# disciples_v1.net
KiCad netlist of a schematic drawn in EAGLE
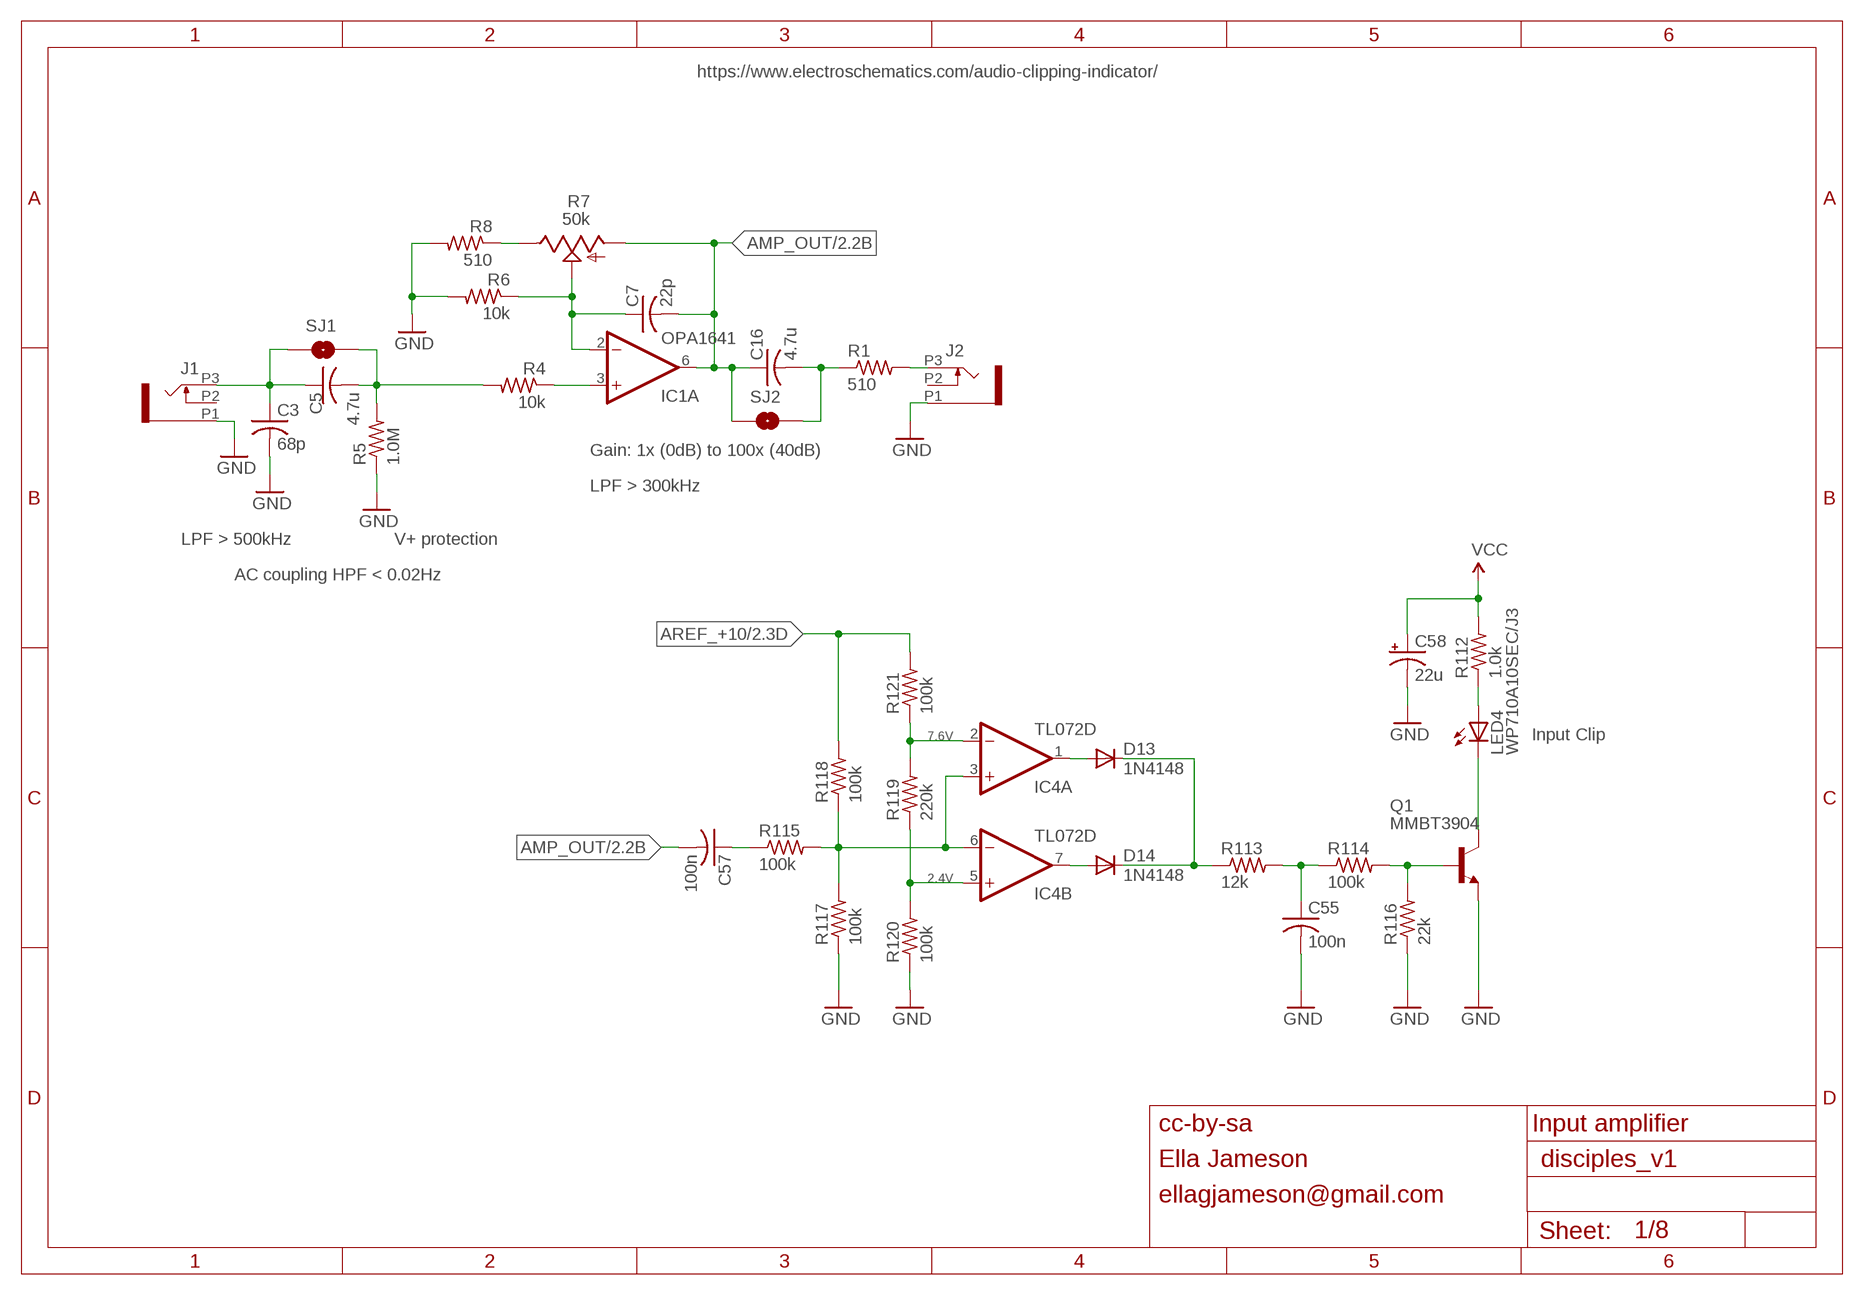
[diagram p0: schematic, sheet 1]
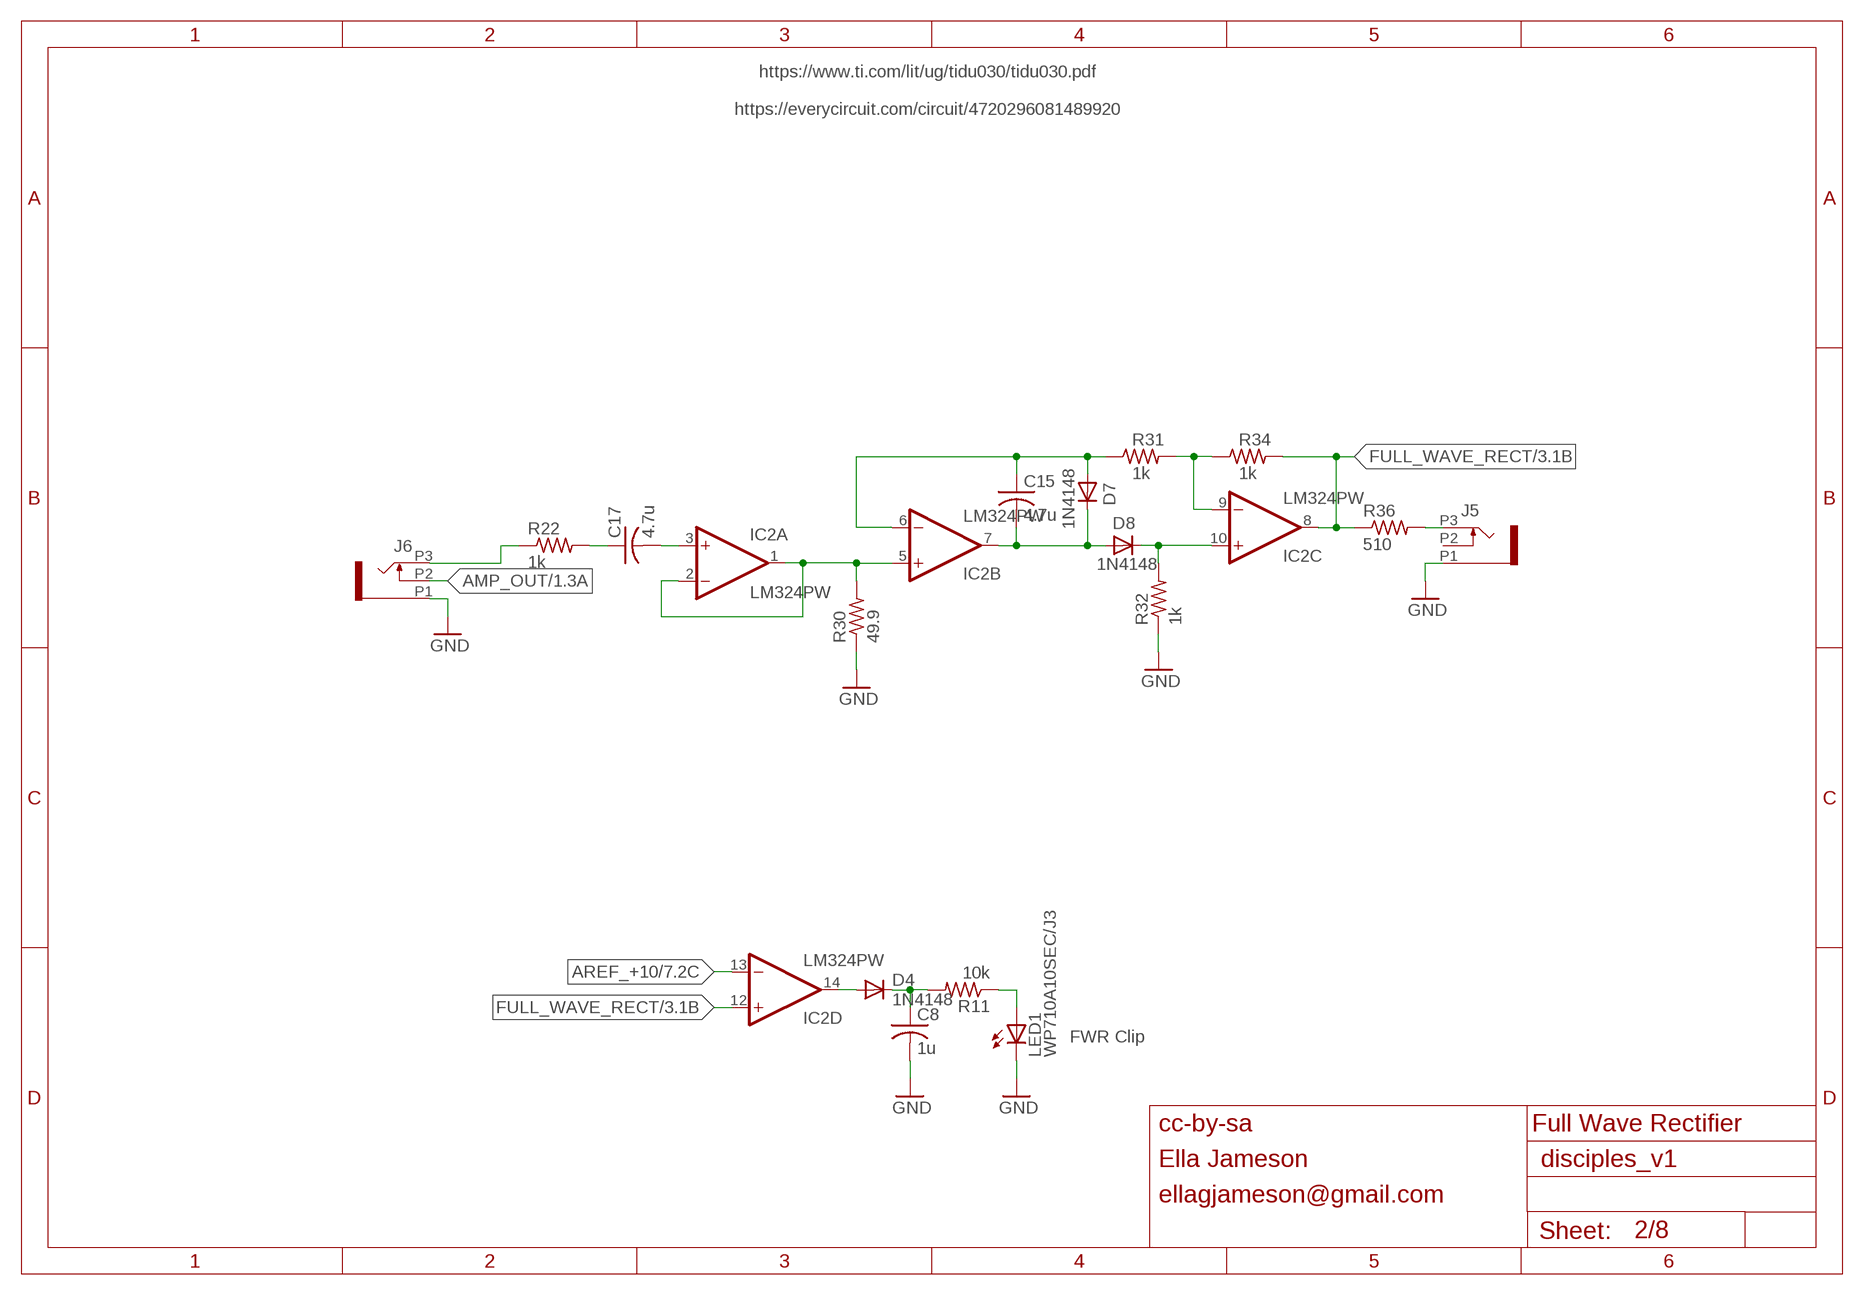
[diagram p1: schematic, sheet 2]
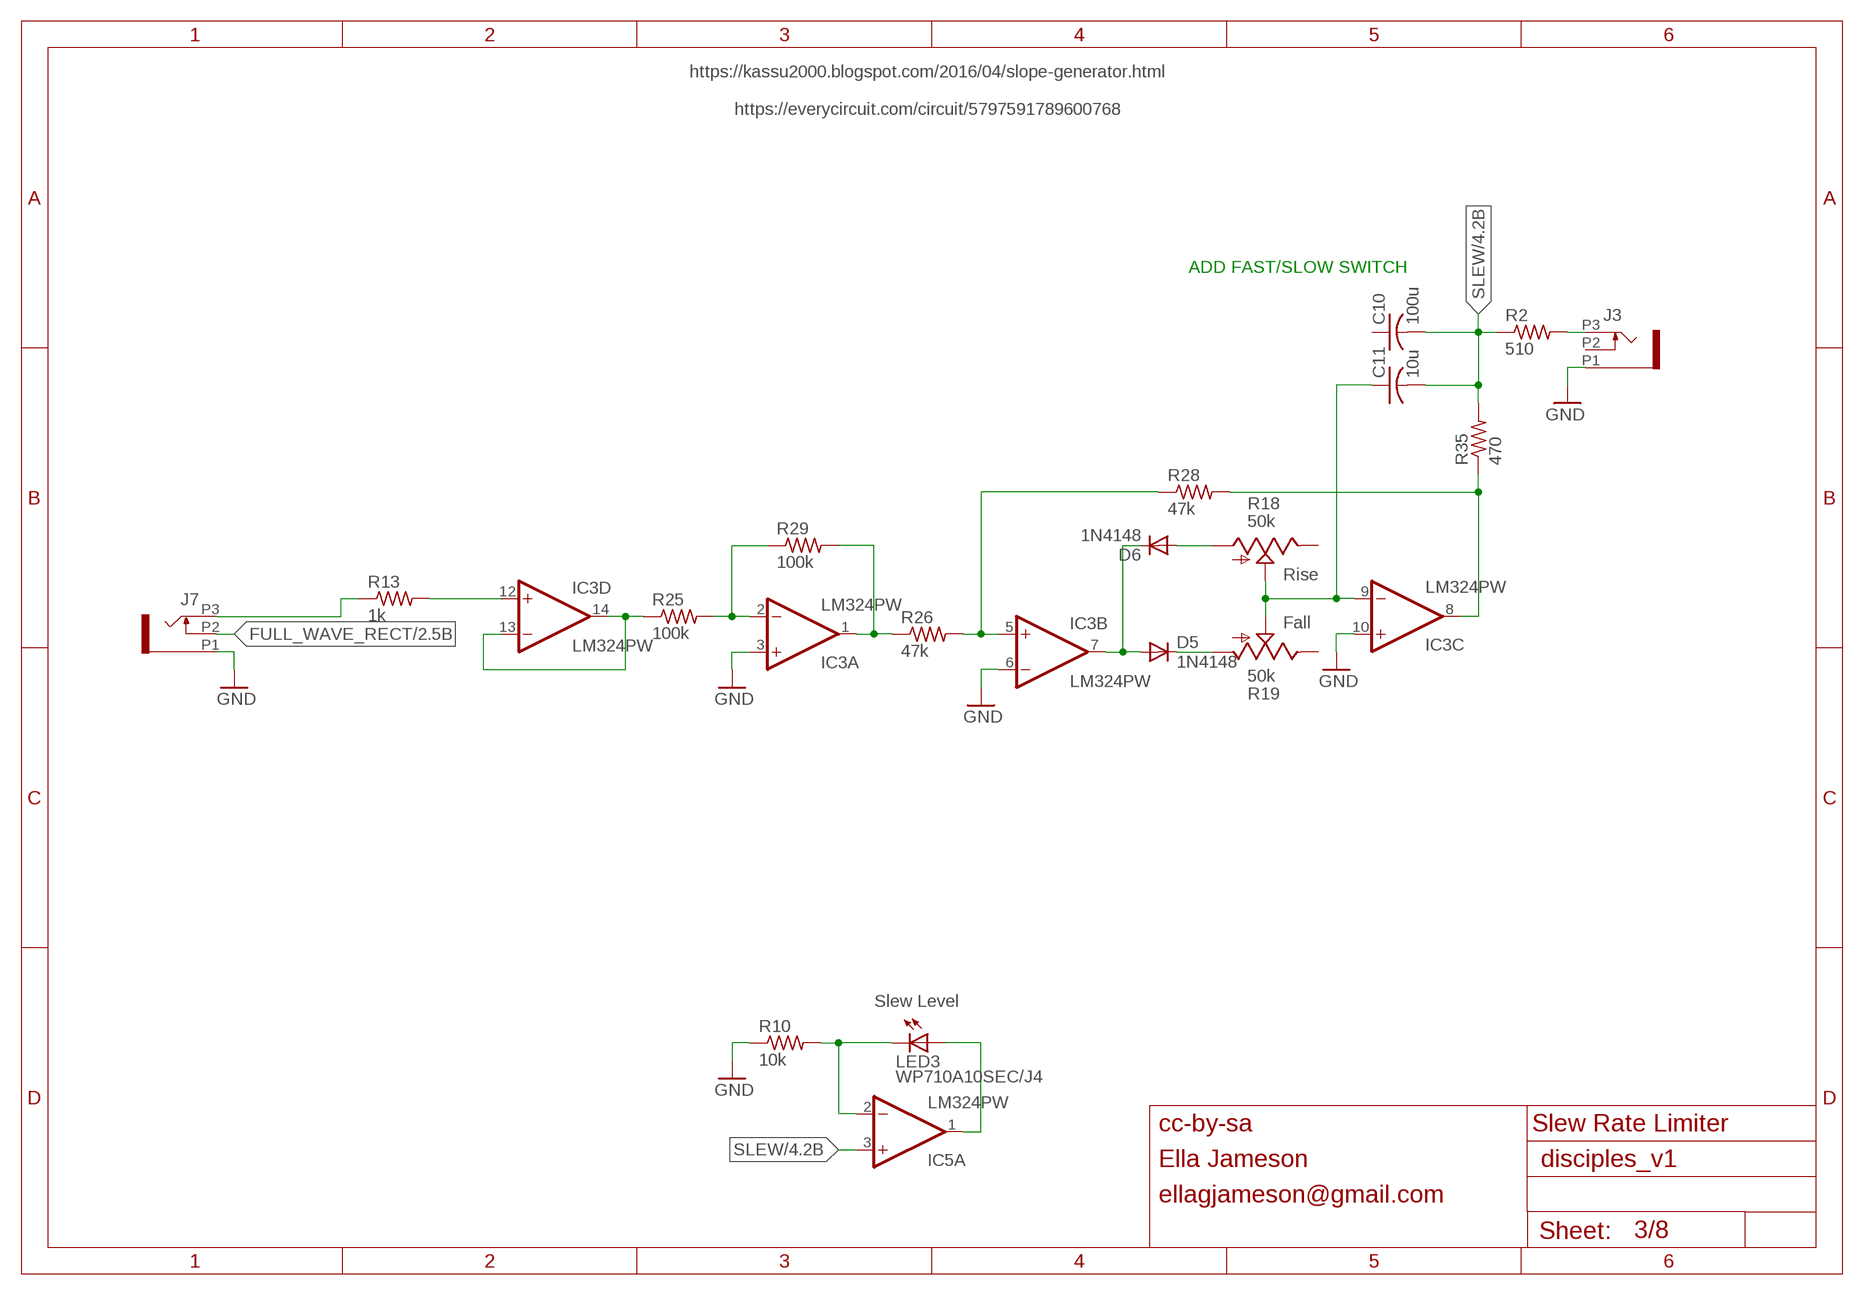
[diagram p2: schematic, sheet 3]
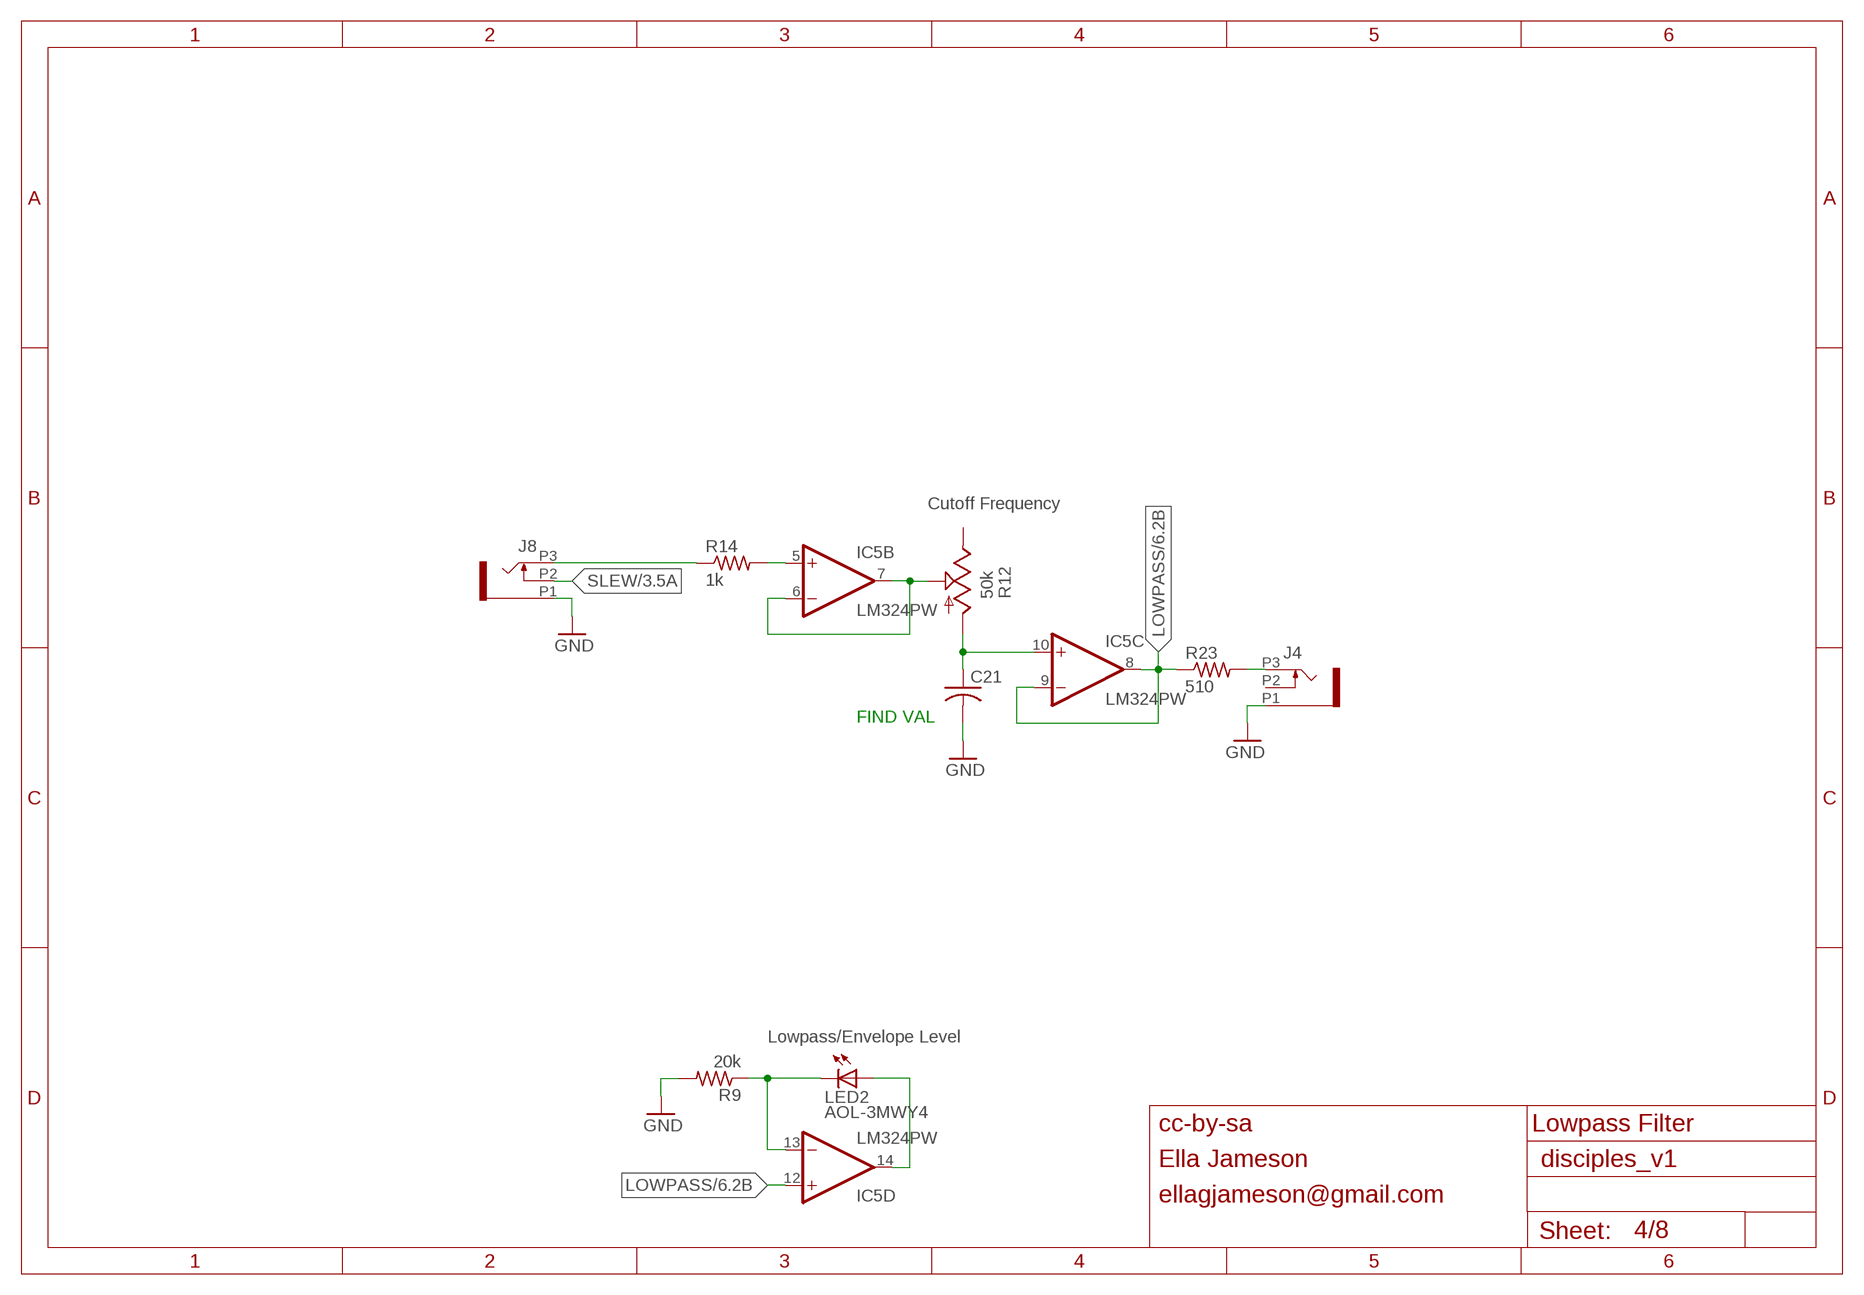
[diagram p3: schematic, sheet 4]
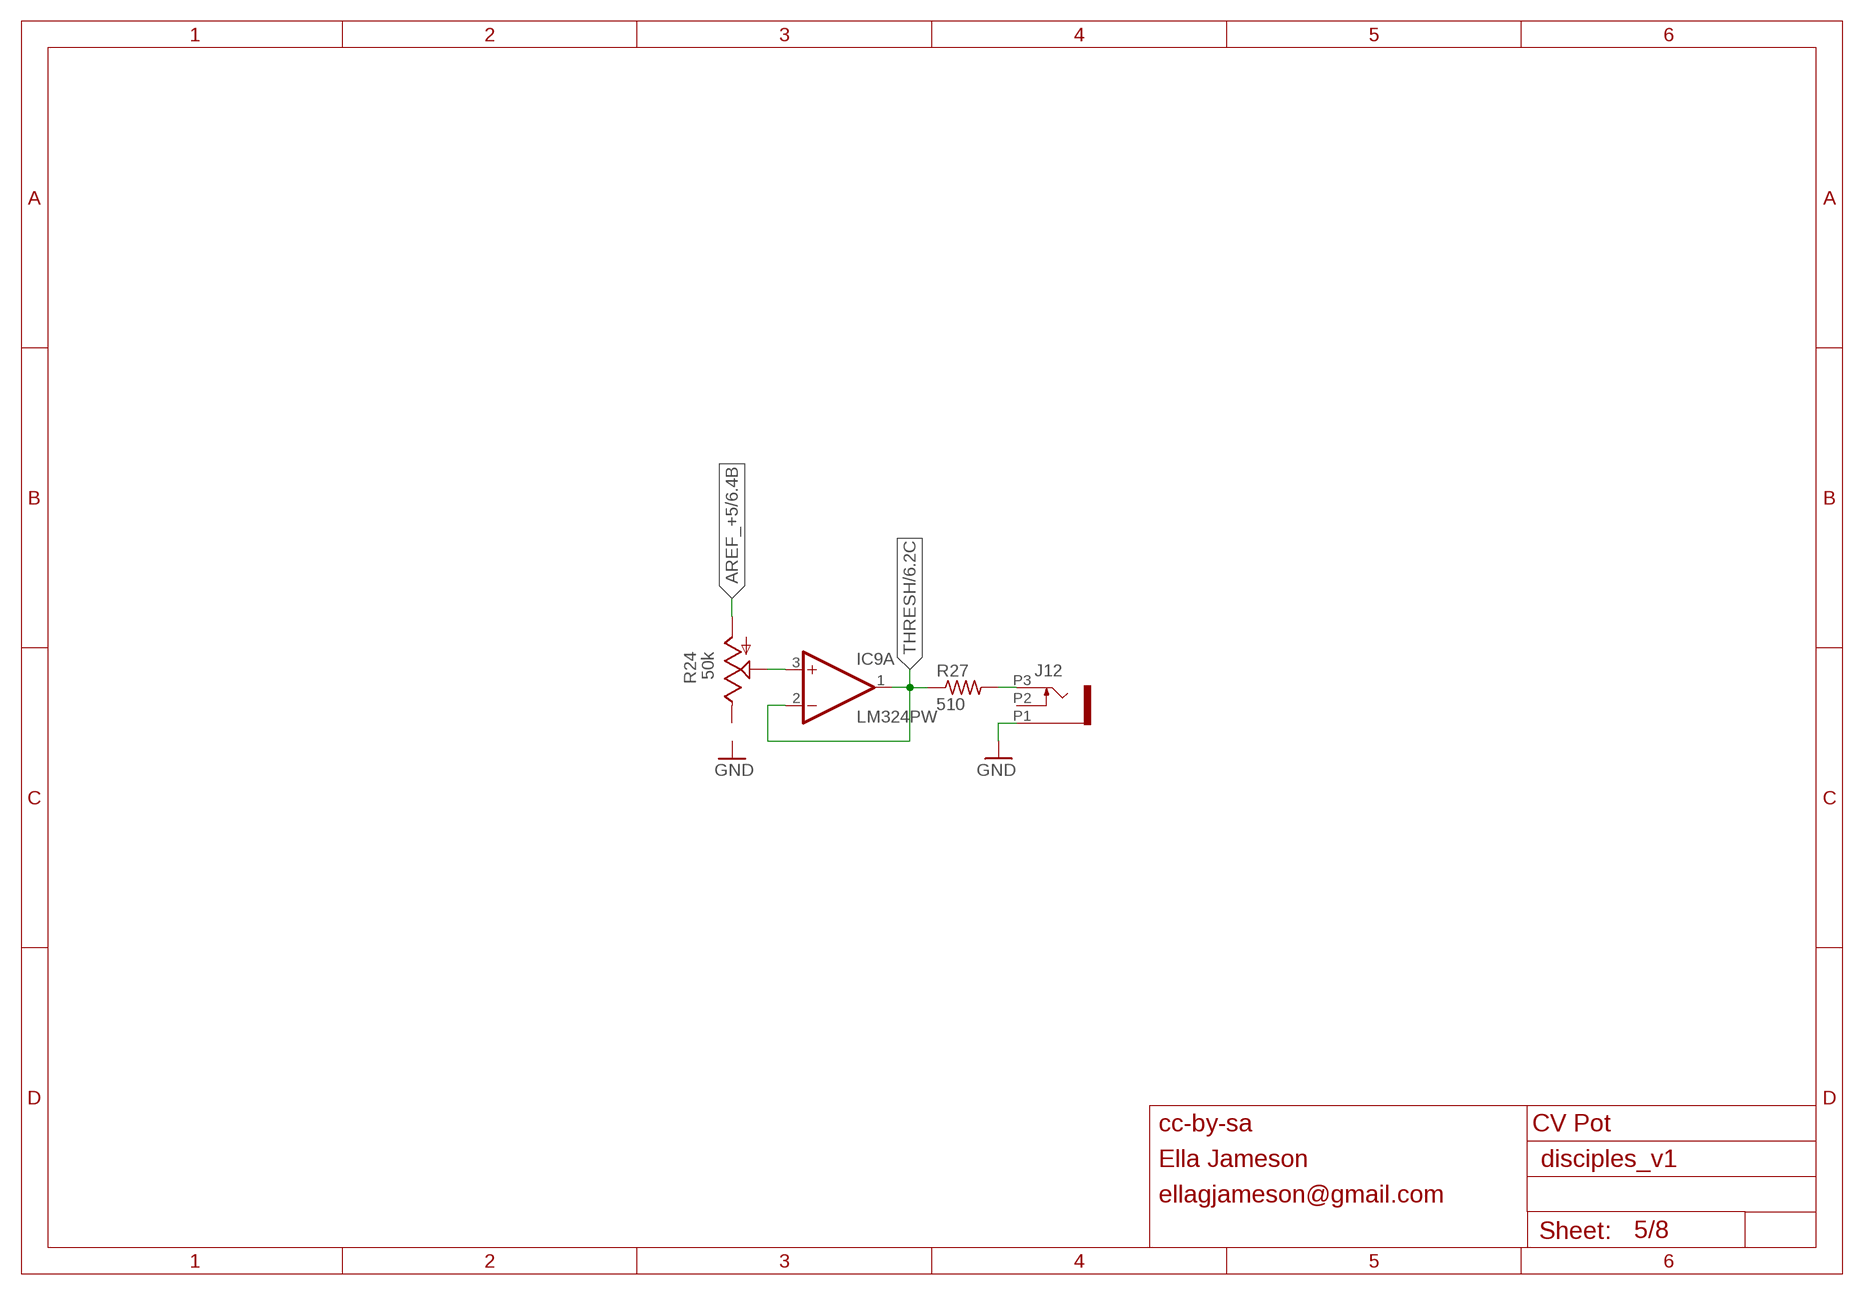
[diagram p4: schematic, sheet 5]
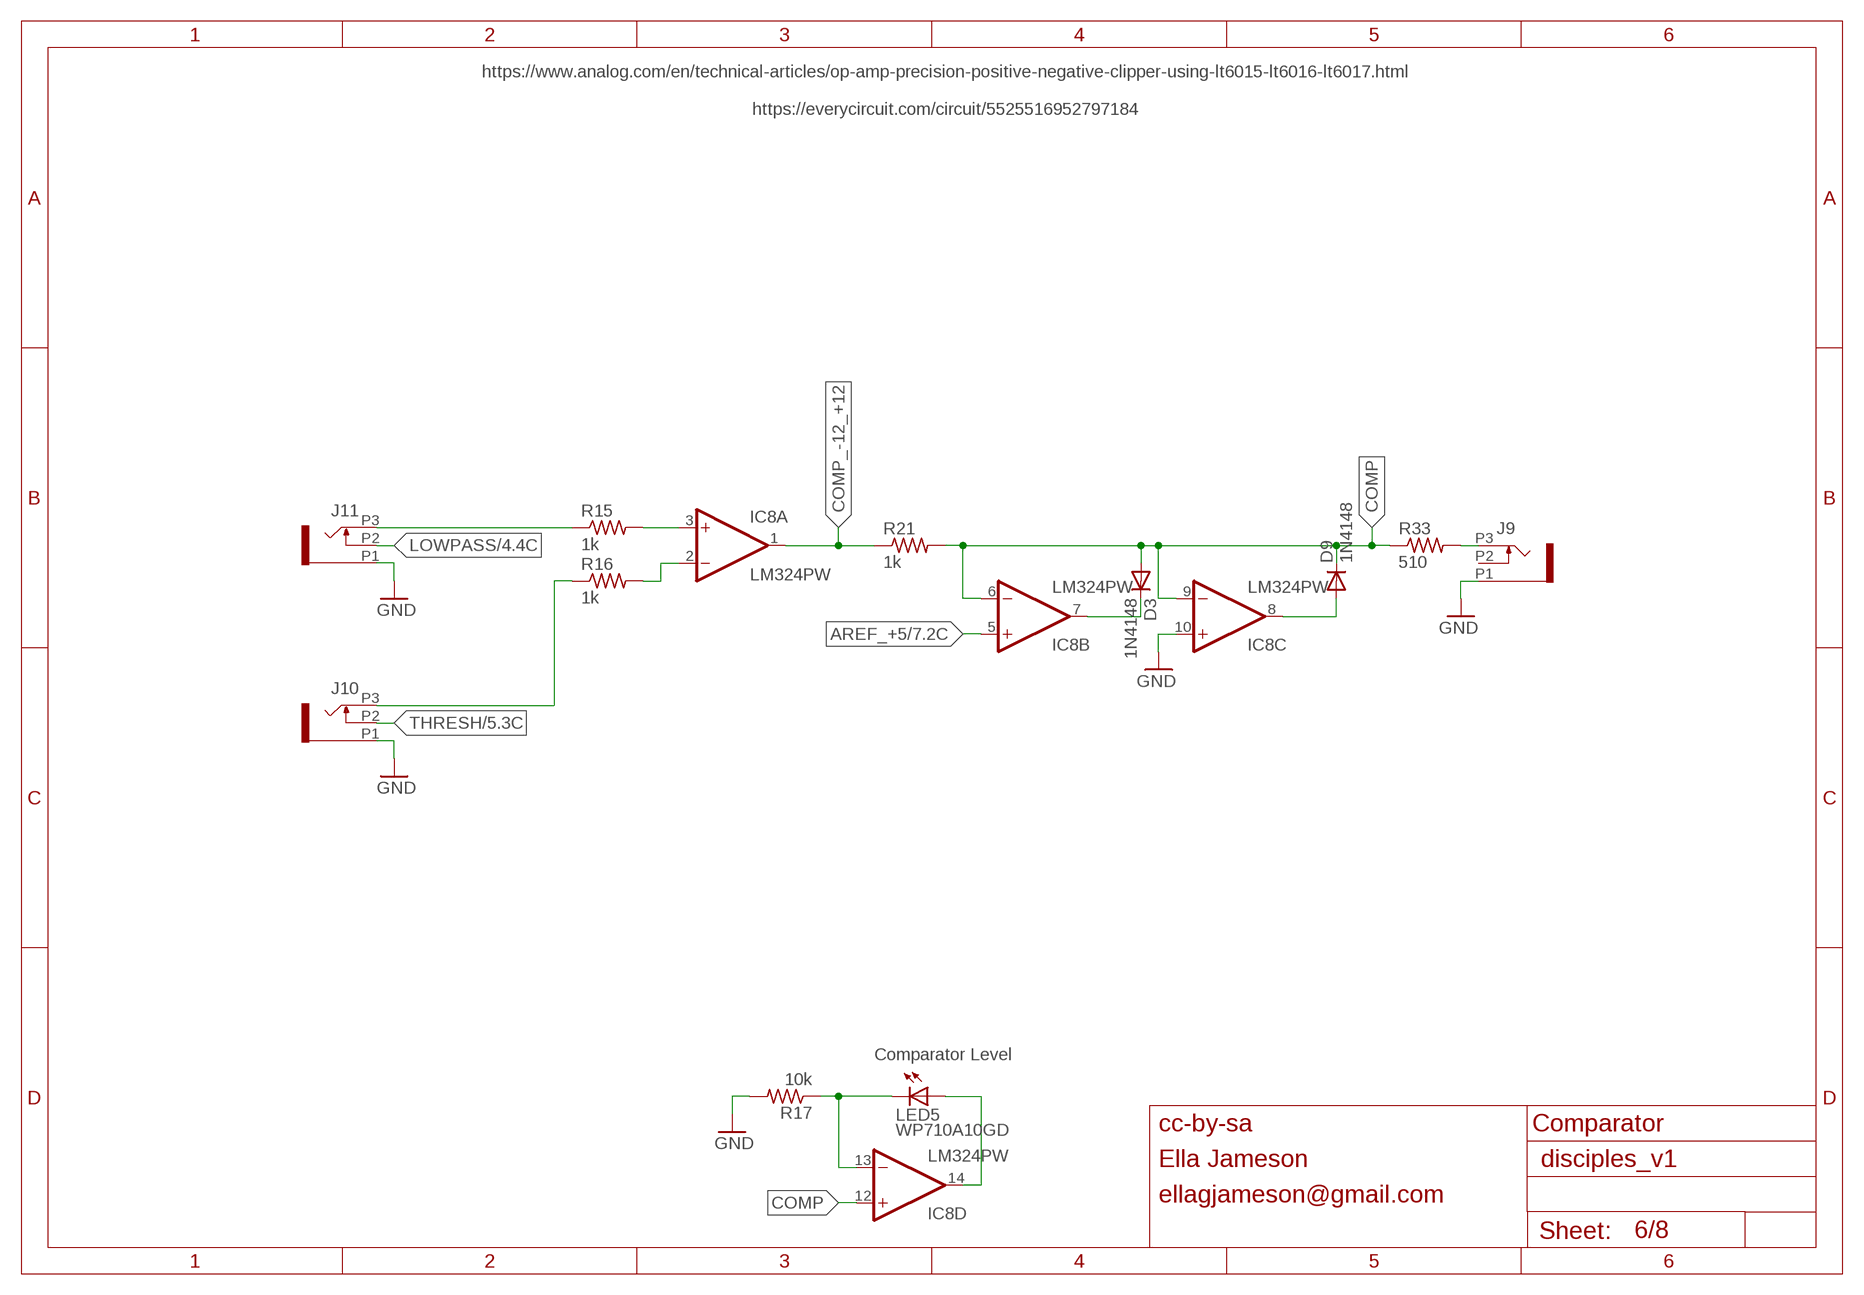
[diagram p5: schematic, sheet 6]
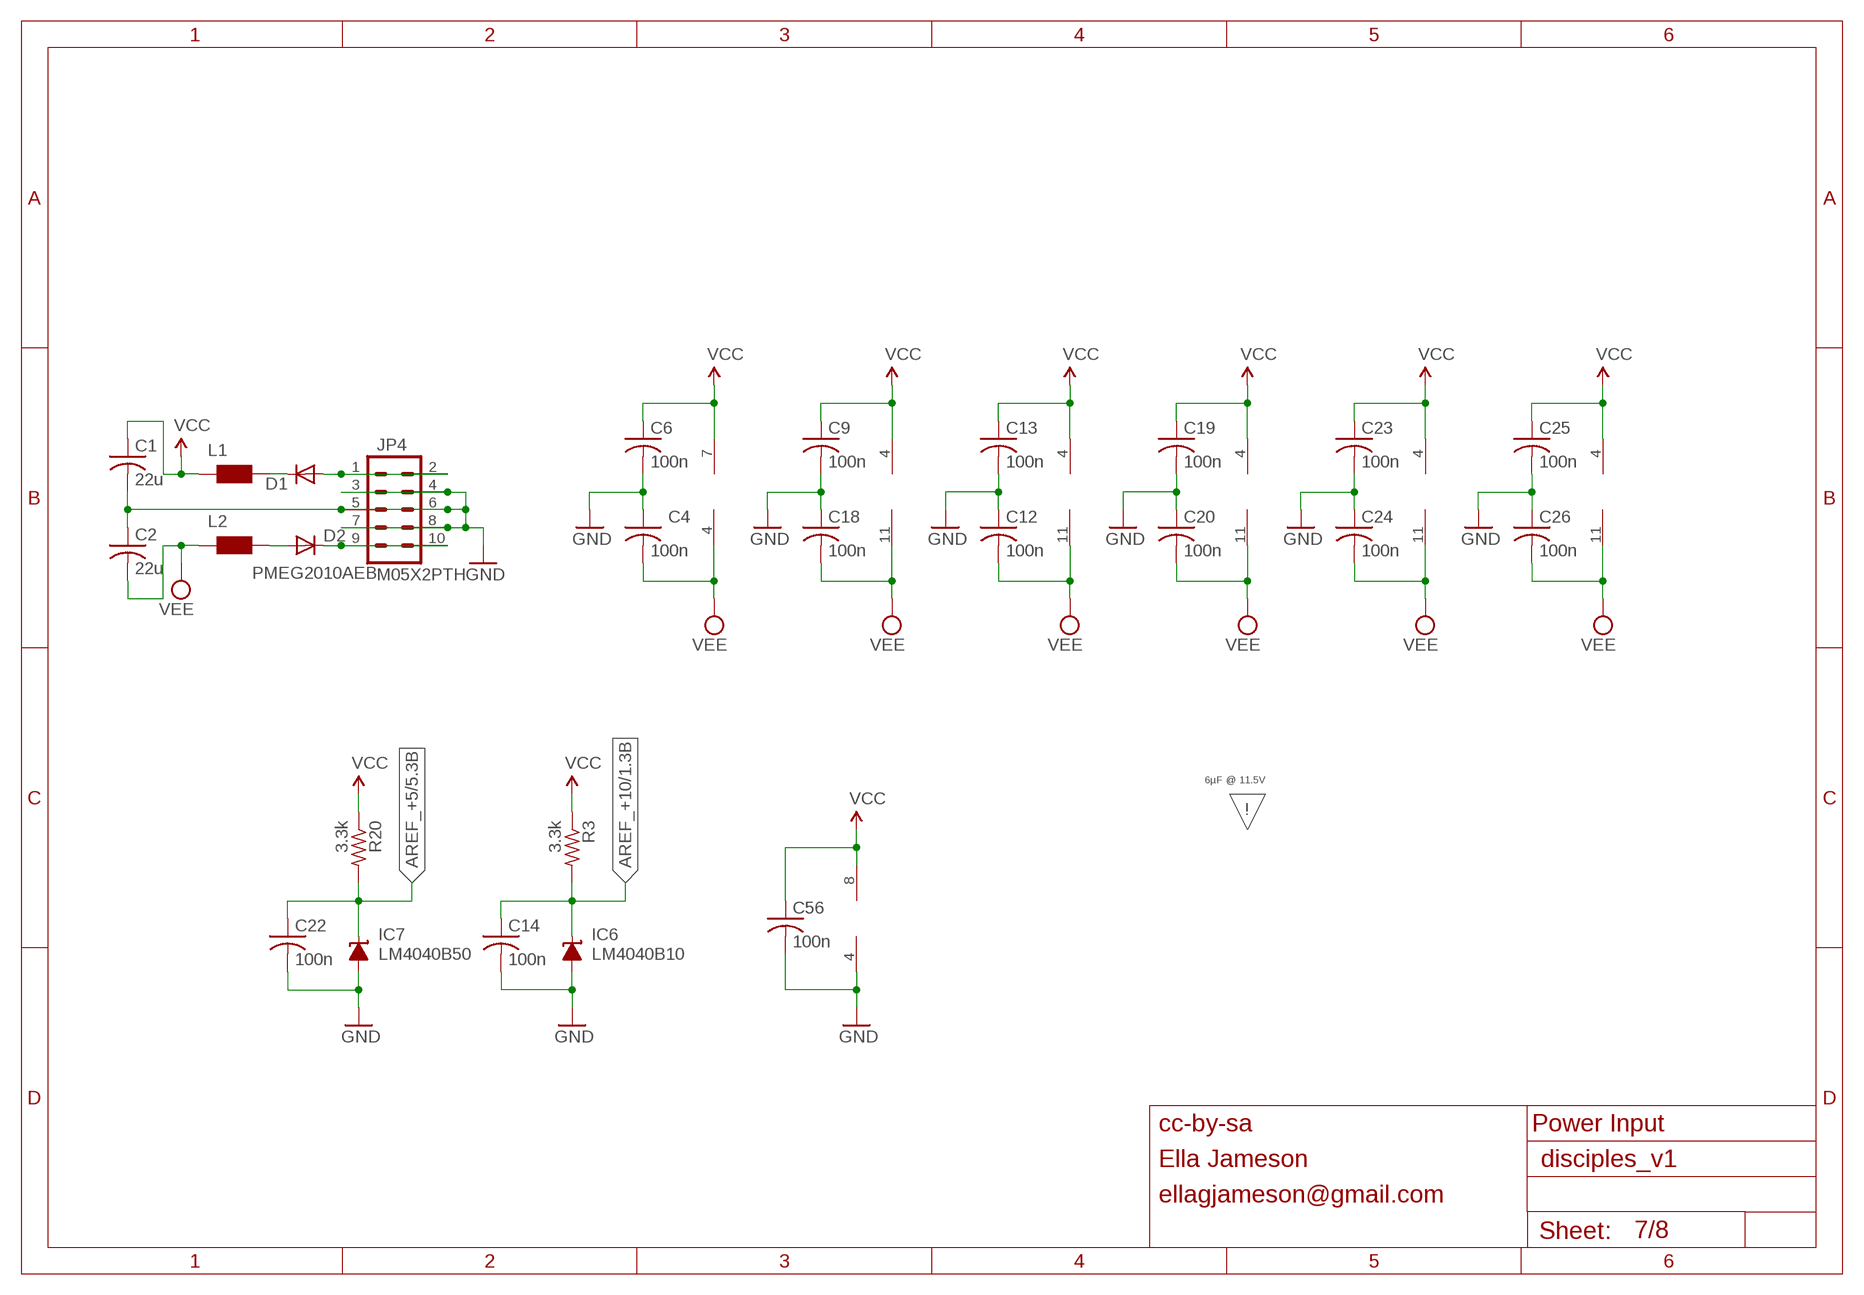
[diagram p6: schematic, sheet 7]
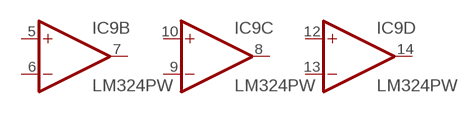
[diagram p7: schematic, sheet 8]

(export (version "E")
  (design (tool "Eeschema 10.0.6"))
  (components
    (comp (ref "D3")
      (value "1N4148")
      (footprint "eagle-import:SOD523")
      (libsource (lib "eagle-import") (part "DIODE-SOD523"))
    )
    (comp (ref "D9")
      (value "1N4148")
      (footprint "eagle-import:SOD523")
      (libsource (lib "eagle-import") (part "DIODE-SOD523"))
    )
    (comp (ref "IC8")
      (value "LM324PW")
      (footprint "eagle-import:TSSOP14")
      (libsource (lib "eagle-import") (part "LM324PW"))
    )
    (comp (ref "J9")
      (value "PJ301_THONKICONN6")
      (footprint "eagle-import:WQP_PJ_301M6")
      (libsource (lib "eagle-import") (part "PJ301_THONKICONN6"))
    )
    (comp (ref "J10")
      (value "PJ301_THONKICONN6")
      (footprint "eagle-import:WQP_PJ_301M6")
      (libsource (lib "eagle-import") (part "PJ301_THONKICONN6"))
    )
    (comp (ref "J11")
      (value "PJ301_THONKICONN6")
      (footprint "eagle-import:WQP_PJ_301M6")
      (libsource (lib "eagle-import") (part "PJ301_THONKICONN6"))
    )
    (comp (ref "LED5")
      (value "WP710A10GD")
      (footprint "eagle-import:LED3MM")
      (libsource (lib "eagle-import") (part "LED3MM"))
    )
    (comp (ref "R15")
      (value "1k")
      (footprint "eagle-import:R0402")
      (libsource (lib "eagle-import") (part "R-US_R0402"))
    )
    (comp (ref "R16")
      (value "1k")
      (footprint "eagle-import:R0402")
      (libsource (lib "eagle-import") (part "R-US_R0402"))
    )
    (comp (ref "R17")
      (value "10k")
      (footprint "eagle-import:R0402")
      (libsource (lib "eagle-import") (part "R-US_R0402"))
    )
    (comp (ref "R21")
      (value "1k")
      (footprint "eagle-import:R0402")
      (libsource (lib "eagle-import") (part "R-US_R0402"))
    )
    (comp (ref "R33")
      (value "510")
      (footprint "eagle-import:R0402")
      (libsource (lib "eagle-import") (part "R-US_R0402"))
    )
    (comp (ref "IC9")
      (value "LM324PW")
      (footprint "eagle-import:TSSOP14")
      (libsource (lib "eagle-import") (part "LM324PW"))
    )
    (comp (ref "J12")
      (value "PJ301_THONKICONN6")
      (footprint "eagle-import:WQP_PJ_301M6")
      (libsource (lib "eagle-import") (part "PJ301_THONKICONN6"))
    )
    (comp (ref "R24")
      (value "50k")
      (footprint "eagle-import:ALPS_POT_VERTICAL_PS")
      (libsource (lib "eagle-import") (part "POT_USVERTICAL_PS"))
    )
    (comp (ref "R27")
      (value "510")
      (footprint "eagle-import:R0402")
      (libsource (lib "eagle-import") (part "R-US_R0402"))
    )
    (comp (ref "C21")
      (value "C-USC0402")
      (footprint "eagle-import:C0402")
      (libsource (lib "eagle-import") (part "C-USC0402"))
    )
    (comp (ref "IC5")
      (value "LM324PW")
      (footprint "eagle-import:TSSOP14")
      (libsource (lib "eagle-import") (part "LM324PW"))
    )
    (comp (ref "J4")
      (value "PJ301_THONKICONN6")
      (footprint "eagle-import:WQP_PJ_301M6")
      (libsource (lib "eagle-import") (part "PJ301_THONKICONN6"))
    )
    (comp (ref "J8")
      (value "PJ301_THONKICONN6")
      (footprint "eagle-import:WQP_PJ_301M6")
      (libsource (lib "eagle-import") (part "PJ301_THONKICONN6"))
    )
    (comp (ref "LED2")
      (value "AOL-3MWY4")
      (footprint "eagle-import:LED3MM")
      (libsource (lib "eagle-import") (part "LED3MM"))
    )
    (comp (ref "R9")
      (value "20k")
      (footprint "eagle-import:R0402")
      (libsource (lib "eagle-import") (part "R-US_R0402"))
    )
    (comp (ref "R12")
      (value "50k")
      (footprint "eagle-import:ALPS_POT_VERTICAL_PS")
      (libsource (lib "eagle-import") (part "POT_USVERTICAL_PS"))
    )
    (comp (ref "R14")
      (value "1k")
      (footprint "eagle-import:R0402")
      (libsource (lib "eagle-import") (part "R-US_R0402"))
    )
    (comp (ref "R23")
      (value "510")
      (footprint "eagle-import:R0402")
      (libsource (lib "eagle-import") (part "R-US_R0402"))
    )
    (comp (ref "C8")
      (value "1u")
      (footprint "eagle-import:C0402")
      (libsource (lib "eagle-import") (part "C-USC0402"))
    )
    (comp (ref "C15")
      (value "4.7u")
      (footprint "eagle-import:C0603")
      (libsource (lib "eagle-import") (part "C-USC0603"))
    )
    (comp (ref "C17")
      (value "4.7u")
      (footprint "eagle-import:C0603")
      (libsource (lib "eagle-import") (part "C-USC0603"))
    )
    (comp (ref "D4")
      (value "1N4148")
      (footprint "eagle-import:SOD523")
      (libsource (lib "eagle-import") (part "DIODE-SOD523"))
    )
    (comp (ref "D7")
      (value "1N4148")
      (footprint "eagle-import:SOD523")
      (libsource (lib "eagle-import") (part "DIODE-SOD523"))
    )
    (comp (ref "D8")
      (value "1N4148")
      (footprint "eagle-import:SOD523")
      (libsource (lib "eagle-import") (part "DIODE-SOD523"))
    )
    (comp (ref "IC2")
      (value "LM324PW")
      (footprint "eagle-import:TSSOP14")
      (libsource (lib "eagle-import") (part "LM324PW"))
    )
    (comp (ref "J5")
      (value "PJ301_THONKICONN6")
      (footprint "eagle-import:WQP_PJ_301M6")
      (libsource (lib "eagle-import") (part "PJ301_THONKICONN6"))
    )
    (comp (ref "J6")
      (value "PJ301_THONKICONN6")
      (footprint "eagle-import:WQP_PJ_301M6")
      (libsource (lib "eagle-import") (part "PJ301_THONKICONN6"))
    )
    (comp (ref "LED1")
      (value "WP710A10SEC/J3")
      (footprint "eagle-import:LED3MM")
      (libsource (lib "eagle-import") (part "LED3MM"))
    )
    (comp (ref "R11")
      (value "10k")
      (footprint "eagle-import:R0402")
      (libsource (lib "eagle-import") (part "R-US_R0402"))
    )
    (comp (ref "R22")
      (value "1k")
      (footprint "eagle-import:R0402")
      (libsource (lib "eagle-import") (part "R-US_R0402"))
    )
    (comp (ref "R30")
      (value "49.9")
      (footprint "eagle-import:R0402")
      (libsource (lib "eagle-import") (part "R-US_R0402"))
    )
    (comp (ref "R31")
      (value "1k")
      (footprint "eagle-import:R0402")
      (libsource (lib "eagle-import") (part "R-US_R0402"))
    )
    (comp (ref "R32")
      (value "1k")
      (footprint "eagle-import:R0402")
      (libsource (lib "eagle-import") (part "R-US_R0402"))
    )
    (comp (ref "R34")
      (value "1k")
      (footprint "eagle-import:R0402")
      (libsource (lib "eagle-import") (part "R-US_R0402"))
    )
    (comp (ref "R36")
      (value "510")
      (footprint "eagle-import:R0402")
      (libsource (lib "eagle-import") (part "R-US_R0402"))
    )
    (comp (ref "C1")
      (value "22u")
      (footprint "eagle-import:C1206")
      (libsource (lib "eagle-import") (part "C-USC1206"))
    )
    (comp (ref "C2")
      (value "22u")
      (footprint "eagle-import:C1206")
      (libsource (lib "eagle-import") (part "C-USC1206"))
    )
    (comp (ref "C4")
      (value "100n")
      (footprint "eagle-import:C0402")
      (libsource (lib "eagle-import") (part "C-USC0402"))
    )
    (comp (ref "C6")
      (value "100n")
      (footprint "eagle-import:C0402")
      (libsource (lib "eagle-import") (part "C-USC0402"))
    )
    (comp (ref "C9")
      (value "100n")
      (footprint "eagle-import:C0402")
      (libsource (lib "eagle-import") (part "C-USC0402"))
    )
    (comp (ref "C12")
      (value "100n")
      (footprint "eagle-import:C0402")
      (libsource (lib "eagle-import") (part "C-USC0402"))
    )
    (comp (ref "C13")
      (value "100n")
      (footprint "eagle-import:C0402")
      (libsource (lib "eagle-import") (part "C-USC0402"))
    )
    (comp (ref "C14")
      (value "100n")
      (footprint "eagle-import:C0603")
      (libsource (lib "eagle-import") (part "C-USC0603"))
    )
    (comp (ref "C18")
      (value "100n")
      (footprint "eagle-import:C0402")
      (libsource (lib "eagle-import") (part "C-USC0402"))
    )
    (comp (ref "C19")
      (value "100n")
      (footprint "eagle-import:C0402")
      (libsource (lib "eagle-import") (part "C-USC0402"))
    )
    (comp (ref "C20")
      (value "100n")
      (footprint "eagle-import:C0402")
      (libsource (lib "eagle-import") (part "C-USC0402"))
    )
    (comp (ref "C22")
      (value "100n")
      (footprint "eagle-import:C0603")
      (libsource (lib "eagle-import") (part "C-USC0603"))
    )
    (comp (ref "C23")
      (value "100n")
      (footprint "eagle-import:C0402")
      (libsource (lib "eagle-import") (part "C-USC0402"))
    )
    (comp (ref "C24")
      (value "100n")
      (footprint "eagle-import:C0402")
      (libsource (lib "eagle-import") (part "C-USC0402"))
    )
    (comp (ref "C25")
      (value "100n")
      (footprint "eagle-import:C0402")
      (libsource (lib "eagle-import") (part "C-USC0402"))
    )
    (comp (ref "C26")
      (value "100n")
      (footprint "eagle-import:C0402")
      (libsource (lib "eagle-import") (part "C-USC0402"))
    )
    (comp (ref "C56")
      (value "100n")
      (footprint "eagle-import:C0603")
      (libsource (lib "eagle-import") (part "C-USC0603"))
    )
    (comp (ref "D1")
      (value "PMEG2010AEB")
      (footprint "eagle-import:SOD523")
      (libsource (lib "eagle-import") (part "DIODE-SOD523"))
    )
    (comp (ref "D2")
      (value "PMEG2010AEB")
      (footprint "eagle-import:SOD523")
      (libsource (lib "eagle-import") (part "DIODE-SOD523"))
    )
    (comp (ref "IC1")
      (value "OPA1641")
      (footprint "eagle-import:MSOP8")
      (libsource (lib "eagle-import") (part "OPA1641"))
    )
    (comp (ref "IC3")
      (value "LM324PW")
      (footprint "eagle-import:TSSOP14")
      (libsource (lib "eagle-import") (part "LM324PW"))
    )
    (comp (ref "IC4")
      (value "TL072D")
      (footprint "eagle-import:SO08")
      (libsource (lib "eagle-import") (part "TL072D"))
    )
    (comp (ref "IC6")
      (value "LM4040B10")
      (footprint "eagle-import:DBZ_R-PDSO-G3")
      (libsource (lib "eagle-import") (part "LM4041DBZB12"))
    )
    (comp (ref "IC7")
      (value "LM4040B50")
      (footprint "eagle-import:DBZ_R-PDSO-G3")
      (libsource (lib "eagle-import") (part "LM4041DBZB12"))
    )
    (comp (ref "JP4")
      (value "M05X2PTH")
      (footprint "eagle-import:AVR_ICSP")
      (libsource (lib "eagle-import") (part "M05X2PTH"))
    )
    (comp (ref "L1")
      (value "WE-CBF_0603")
      (footprint "eagle-import:0603")
      (libsource (lib "eagle-import") (part "WE-CBF_0603"))
    )
    (comp (ref "L2")
      (value "WE-CBF_0603")
      (footprint "eagle-import:0603")
      (libsource (lib "eagle-import") (part "WE-CBF_0603"))
    )
    (comp (ref "R3")
      (value "3.3k")
      (footprint "eagle-import:R0603")
      (libsource (lib "eagle-import") (part "R-US_R0603"))
    )
    (comp (ref "R20")
      (value "3.3k")
      (footprint "eagle-import:R0603")
      (libsource (lib "eagle-import") (part "R-US_R0603"))
    )
    (comp (ref "C10")
      (value "100u")
      (footprint "eagle-import:C0402")
      (libsource (lib "eagle-import") (part "C-USC0402"))
    )
    (comp (ref "C11")
      (value "10u")
      (footprint "eagle-import:C0402")
      (libsource (lib "eagle-import") (part "C-USC0402"))
    )
    (comp (ref "D5")
      (value "1N4148")
      (footprint "eagle-import:SOD523")
      (libsource (lib "eagle-import") (part "DIODE-SOD523"))
    )
    (comp (ref "D6")
      (value "1N4148")
      (footprint "eagle-import:SOD523")
      (libsource (lib "eagle-import") (part "DIODE-SOD523"))
    )
    (comp (ref "J3")
      (value "PJ301_THONKICONN6")
      (footprint "eagle-import:WQP_PJ_301M6")
      (libsource (lib "eagle-import") (part "PJ301_THONKICONN6"))
    )
    (comp (ref "J7")
      (value "PJ301_THONKICONN6")
      (footprint "eagle-import:WQP_PJ_301M6")
      (libsource (lib "eagle-import") (part "PJ301_THONKICONN6"))
    )
    (comp (ref "LED3")
      (value "WP710A10SEC/J4")
      (footprint "eagle-import:LED3MM")
      (libsource (lib "eagle-import") (part "LED3MM"))
    )
    (comp (ref "R2")
      (value "510")
      (footprint "eagle-import:R0402")
      (libsource (lib "eagle-import") (part "R-US_R0402"))
    )
    (comp (ref "R10")
      (value "10k")
      (footprint "eagle-import:R0402")
      (libsource (lib "eagle-import") (part "R-US_R0402"))
    )
    (comp (ref "R13")
      (value "1k")
      (footprint "eagle-import:R0402")
      (libsource (lib "eagle-import") (part "R-US_R0402"))
    )
    (comp (ref "R18")
      (value "50k")
      (footprint "eagle-import:ALPS_POT_VERTICAL_PS")
      (libsource (lib "eagle-import") (part "POT_USVERTICAL_PS"))
    )
    (comp (ref "R19")
      (value "50k")
      (footprint "eagle-import:ALPS_POT_VERTICAL_PS")
      (libsource (lib "eagle-import") (part "POT_USVERTICAL_PS"))
    )
    (comp (ref "R25")
      (value "100k")
      (footprint "eagle-import:R0402")
      (libsource (lib "eagle-import") (part "R-US_R0402"))
    )
    (comp (ref "R26")
      (value "47k")
      (footprint "eagle-import:R0402")
      (libsource (lib "eagle-import") (part "R-US_R0402"))
    )
    (comp (ref "R28")
      (value "47k")
      (footprint "eagle-import:R0402")
      (libsource (lib "eagle-import") (part "R-US_R0402"))
    )
    (comp (ref "R29")
      (value "100k")
      (footprint "eagle-import:R0402")
      (libsource (lib "eagle-import") (part "R-US_R0402"))
    )
    (comp (ref "R35")
      (value "470")
      (footprint "eagle-import:R0402")
      (libsource (lib "eagle-import") (part "R-US_R0402"))
    )
    (comp (ref "C3")
      (value "68p")
      (footprint "eagle-import:C0402")
      (libsource (lib "eagle-import") (part "C-USC0402"))
    )
    (comp (ref "C5")
      (value "4.7u")
      (footprint "eagle-import:C0603")
      (libsource (lib "eagle-import") (part "C-USC0603"))
    )
    (comp (ref "C7")
      (value "22p")
      (footprint "eagle-import:C0402")
      (libsource (lib "eagle-import") (part "C-USC0402"))
    )
    (comp (ref "C16")
      (value "4.7u")
      (footprint "eagle-import:C0603")
      (libsource (lib "eagle-import") (part "C-USC0603"))
    )
    (comp (ref "C55")
      (value "100n")
      (footprint "eagle-import:C0603")
      (libsource (lib "eagle-import") (part "C-USC0603"))
    )
    (comp (ref "C57")
      (value "100n")
      (footprint "eagle-import:C0603")
      (libsource (lib "eagle-import") (part "C-USC0603"))
    )
    (comp (ref "C58")
      (value "22u")
      (footprint "eagle-import:PANASONIC_C")
      (libsource (lib "eagle-import") (part "CPOL-USC"))
    )
    (comp (ref "D13")
      (value "1N4148")
      (footprint "eagle-import:SOD323-W")
      (libsource (lib "eagle-import") (part "DIODE-SOD323-W"))
    )
    (comp (ref "D14")
      (value "1N4148")
      (footprint "eagle-import:SOD323-W")
      (libsource (lib "eagle-import") (part "DIODE-SOD323-W"))
    )
    (comp (ref "J1")
      (value "PJ301_THONKICONN6")
      (footprint "eagle-import:WQP_PJ_301M6")
      (libsource (lib "eagle-import") (part "PJ301_THONKICONN6"))
    )
    (comp (ref "J2")
      (value "PJ301_THONKICONN6")
      (footprint "eagle-import:WQP_PJ_301M6")
      (libsource (lib "eagle-import") (part "PJ301_THONKICONN6"))
    )
    (comp (ref "LED4")
      (value "WP710A10SEC/J3")
      (footprint "eagle-import:LED3MM")
      (libsource (lib "eagle-import") (part "LED3MM"))
    )
    (comp (ref "Q1")
      (value "MMBT3904")
      (footprint "eagle-import:SOT23-BEC")
      (libsource (lib "eagle-import") (part "-NPN-SOT23-BECMMBT3904LT1"))
    )
    (comp (ref "R1")
      (value "510")
      (footprint "eagle-import:R0402")
      (libsource (lib "eagle-import") (part "R-US_R0402"))
    )
    (comp (ref "R4")
      (value "10k")
      (footprint "eagle-import:R0402")
      (libsource (lib "eagle-import") (part "R-US_R0402"))
    )
    (comp (ref "R5")
      (value "1.0M")
      (footprint "eagle-import:R0402")
      (libsource (lib "eagle-import") (part "R-US_R0402"))
    )
    (comp (ref "R6")
      (value "10k")
      (footprint "eagle-import:R0402")
      (libsource (lib "eagle-import") (part "R-US_R0402"))
    )
    (comp (ref "R7")
      (value "50k")
      (footprint "eagle-import:ALPS_POT_VERTICAL_PS")
      (libsource (lib "eagle-import") (part "POT_USVERTICAL_PS"))
    )
    (comp (ref "R8")
      (value "510")
      (footprint "eagle-import:R0402")
      (libsource (lib "eagle-import") (part "R-US_R0402"))
    )
    (comp (ref "R112")
      (value "1.0k")
      (footprint "eagle-import:R0603")
      (libsource (lib "eagle-import") (part "R-US_R0603"))
    )
    (comp (ref "R113")
      (value "12k")
      (footprint "eagle-import:R0603")
      (libsource (lib "eagle-import") (part "R-US_R0603"))
    )
    (comp (ref "R114")
      (value "100k")
      (footprint "eagle-import:R0603")
      (libsource (lib "eagle-import") (part "R-US_R0603"))
    )
    (comp (ref "R115")
      (value "100k")
      (footprint "eagle-import:R0603")
      (libsource (lib "eagle-import") (part "R-US_R0603"))
    )
    (comp (ref "R116")
      (value "22k")
      (footprint "eagle-import:R0603")
      (libsource (lib "eagle-import") (part "R-US_R0603"))
    )
    (comp (ref "R117")
      (value "100k")
      (footprint "eagle-import:R0603")
      (libsource (lib "eagle-import") (part "R-US_R0603"))
    )
    (comp (ref "R118")
      (value "100k")
      (footprint "eagle-import:R0603")
      (libsource (lib "eagle-import") (part "R-US_R0603"))
    )
    (comp (ref "R119")
      (value "220k")
      (footprint "eagle-import:R0603")
      (libsource (lib "eagle-import") (part "R-US_R0603"))
    )
    (comp (ref "R120")
      (value "100k")
      (footprint "eagle-import:R0603")
      (libsource (lib "eagle-import") (part "R-US_R0603"))
    )
    (comp (ref "R121")
      (value "100k")
      (footprint "eagle-import:R0603")
      (libsource (lib "eagle-import") (part "R-US_R0603"))
    )
    (comp (ref "SJ1")
      (value "SOLDERJUMPERNC")
      (footprint "eagle-import:SJ_2S")
      (libsource (lib "eagle-import") (part "SOLDERJUMPERNC"))
    )
    (comp (ref "SJ2")
      (value "SOLDERJUMPERNC")
      (footprint "eagle-import:SJ_2S")
      (libsource (lib "eagle-import") (part "SOLDERJUMPERNC"))
    )
  )
  (nets
    (net (code "1") (name "AMP_OUT") (class "Default")
      (node (ref "C16") (pin "1") (pinfunction "1_1") (pintype "passive"))
      (node (ref "C57") (pin "2") (pinfunction "2_2") (pintype "passive"))
      (node (ref "C7") (pin "2") (pinfunction "2_2") (pintype "passive"))
      (node (ref "IC1") (pin "6") (pinfunction "OUT_6") (pintype "output"))
      (node (ref "J6") (pin "P2") (pinfunction "2_P2") (pintype "passive"))
      (node (ref "R7") (pin "P$3") (pinfunction "A_P$3") (pintype "passive"))
      (node (ref "SJ2") (pin "1") (pinfunction "1_1") (pintype "passive"))
    )
    (net (code "2") (name "AREF_+5") (class "Default")
      (node (ref "C22") (pin "1") (pinfunction "1_1") (pintype "passive"))
      (node (ref "IC7") (pin "1") (pinfunction "C_1") (pintype "passive"))
      (node (ref "IC8") (pin "5") (pinfunction "+IN_5") (pintype "input"))
      (node (ref "R20") (pin "2") (pinfunction "2_2") (pintype "passive"))
      (node (ref "R24") (pin "P$3") (pinfunction "A_P$3") (pintype "passive"))
    )
    (net (code "3") (name "AREF_+10") (class "Default")
      (node (ref "C14") (pin "1") (pinfunction "1_1") (pintype "passive"))
      (node (ref "IC2") (pin "13") (pinfunction "-IN_13") (pintype "input"))
      (node (ref "IC6") (pin "1") (pinfunction "C_1") (pintype "passive"))
      (node (ref "R118") (pin "2") (pinfunction "2_2") (pintype "passive"))
      (node (ref "R121") (pin "2") (pinfunction "2_2") (pintype "passive"))
      (node (ref "R3") (pin "2") (pinfunction "2_2") (pintype "passive"))
    )
    (net (code "4") (name "COMP") (class "Default")
      (node (ref "D3") (pin "A") (pinfunction "A_A") (pintype "passive"))
      (node (ref "D9") (pin "C") (pinfunction "C_C") (pintype "passive"))
      (node (ref "IC8") (pin "12") (pinfunction "+IN_12") (pintype "input"))
      (node (ref "IC8") (pin "6") (pinfunction "-IN_6") (pintype "input"))
      (node (ref "IC8") (pin "9") (pinfunction "-IN_9") (pintype "input"))
      (node (ref "R21") (pin "2") (pinfunction "2_2") (pintype "passive"))
      (node (ref "R33") (pin "1") (pinfunction "1_1") (pintype "passive"))
    )
    (net (code "5") (name "COMP_-12_+12") (class "Default")
      (node (ref "IC8") (pin "1") (pinfunction "OUT_1") (pintype "output"))
      (node (ref "R21") (pin "1") (pinfunction "1_1") (pintype "passive"))
    )
    (net (code "6") (name "FULL_WAVE_RECT") (class "Default")
      (node (ref "IC2") (pin "12") (pinfunction "+IN_12") (pintype "input"))
      (node (ref "IC2") (pin "8") (pinfunction "OUT_8") (pintype "output"))
      (node (ref "J7") (pin "P2") (pinfunction "2_P2") (pintype "passive"))
      (node (ref "R34") (pin "2") (pinfunction "2_2") (pintype "passive"))
      (node (ref "R36") (pin "1") (pinfunction "1_1") (pintype "passive"))
    )
    (net (code "7") (name "GND") (class "Default")
      (node (ref "C1") (pin "2") (pinfunction "2_2") (pintype "passive"))
      (node (ref "C12") (pin "1") (pinfunction "1_1") (pintype "passive"))
      (node (ref "C13") (pin "2") (pinfunction "2_2") (pintype "passive"))
      (node (ref "C14") (pin "2") (pinfunction "2_2") (pintype "passive"))
      (node (ref "C18") (pin "1") (pinfunction "1_1") (pintype "passive"))
      (node (ref "C19") (pin "2") (pinfunction "2_2") (pintype "passive"))
      (node (ref "C2") (pin "1") (pinfunction "1_1") (pintype "passive"))
      (node (ref "C20") (pin "1") (pinfunction "1_1") (pintype "passive"))
      (node (ref "C21") (pin "2") (pinfunction "2_2") (pintype "passive"))
      (node (ref "C22") (pin "2") (pinfunction "2_2") (pintype "passive"))
      (node (ref "C23") (pin "2") (pinfunction "2_2") (pintype "passive"))
      (node (ref "C24") (pin "1") (pinfunction "1_1") (pintype "passive"))
      (node (ref "C25") (pin "2") (pinfunction "2_2") (pintype "passive"))
      (node (ref "C26") (pin "1") (pinfunction "1_1") (pintype "passive"))
      (node (ref "C3") (pin "2") (pinfunction "2_2") (pintype "passive"))
      (node (ref "C4") (pin "1") (pinfunction "1_1") (pintype "passive"))
      (node (ref "C55") (pin "2") (pinfunction "2_2") (pintype "passive"))
      (node (ref "C56") (pin "2") (pinfunction "2_2") (pintype "passive"))
      (node (ref "C58") (pin "-") (pinfunction "-_-") (pintype "passive"))
      (node (ref "C6") (pin "2") (pinfunction "2_2") (pintype "passive"))
      (node (ref "C8") (pin "2") (pinfunction "2_2") (pintype "passive"))
      (node (ref "C9") (pin "2") (pinfunction "2_2") (pintype "passive"))
      (node (ref "IC3") (pin "10") (pinfunction "+IN_10") (pintype "input"))
      (node (ref "IC3") (pin "3") (pinfunction "+IN_3") (pintype "input"))
      (node (ref "IC3") (pin "6") (pinfunction "-IN_6") (pintype "input"))
      (node (ref "IC4") (pin "4") (pinfunction "V-_4") (pintype "power_in"))
      (node (ref "IC6") (pin "2") (pinfunction "A_2") (pintype "passive"))
      (node (ref "IC7") (pin "2") (pinfunction "A_2") (pintype "passive"))
      (node (ref "IC8") (pin "10") (pinfunction "+IN_10") (pintype "input"))
      (node (ref "J1") (pin "P1") (pinfunction "1_P1") (pintype "passive"))
      (node (ref "J10") (pin "P1") (pinfunction "1_P1") (pintype "passive"))
      (node (ref "J11") (pin "P1") (pinfunction "1_P1") (pintype "passive"))
      (node (ref "J12") (pin "P1") (pinfunction "1_P1") (pintype "passive"))
      (node (ref "J2") (pin "P1") (pinfunction "1_P1") (pintype "passive"))
      (node (ref "J3") (pin "P1") (pinfunction "1_P1") (pintype "passive"))
      (node (ref "J4") (pin "P1") (pinfunction "1_P1") (pintype "passive"))
      (node (ref "J5") (pin "P1") (pinfunction "1_P1") (pintype "passive"))
      (node (ref "J6") (pin "P1") (pinfunction "1_P1") (pintype "passive"))
      (node (ref "J7") (pin "P1") (pinfunction "1_P1") (pintype "passive"))
      (node (ref "J8") (pin "P1") (pinfunction "1_P1") (pintype "passive"))
      (node (ref "J9") (pin "P1") (pinfunction "1_P1") (pintype "passive"))
      (node (ref "JP4") (pin "3") (pinfunction "3_3") (pintype "passive"))
      (node (ref "JP4") (pin "4") (pinfunction "4_4") (pintype "passive"))
      (node (ref "JP4") (pin "5") (pinfunction "5_5") (pintype "passive"))
      (node (ref "JP4") (pin "6") (pinfunction "6_6") (pintype "passive"))
      (node (ref "JP4") (pin "7") (pinfunction "7_7") (pintype "passive"))
      (node (ref "JP4") (pin "8") (pinfunction "8_8") (pintype "passive"))
      (node (ref "LED1") (pin "K") (pinfunction "C_K") (pintype "passive"))
      (node (ref "Q1") (pin "E") (pinfunction "E_E") (pintype "passive"))
      (node (ref "R10") (pin "1") (pinfunction "1_1") (pintype "passive"))
      (node (ref "R116") (pin "1") (pinfunction "1_1") (pintype "passive"))
      (node (ref "R117") (pin "1") (pinfunction "1_1") (pintype "passive"))
      (node (ref "R120") (pin "1") (pinfunction "1_1") (pintype "passive"))
      (node (ref "R17") (pin "2") (pinfunction "2_2") (pintype "passive"))
      (node (ref "R30") (pin "1") (pinfunction "1_1") (pintype "passive"))
      (node (ref "R32") (pin "1") (pinfunction "1_1") (pintype "passive"))
      (node (ref "R5") (pin "1") (pinfunction "1_1") (pintype "passive"))
      (node (ref "R6") (pin "2") (pinfunction "2_2") (pintype "passive"))
      (node (ref "R8") (pin "2") (pinfunction "2_2") (pintype "passive"))
      (node (ref "R9") (pin "2") (pinfunction "2_2") (pintype "passive"))
    )
    (net (code "8") (name "LOWPASS") (class "Default")
      (node (ref "IC5") (pin "12") (pinfunction "+IN_12") (pintype "input"))
      (node (ref "IC5") (pin "8") (pinfunction "OUT_8") (pintype "output"))
      (node (ref "IC5") (pin "9") (pinfunction "-IN_9") (pintype "input"))
      (node (ref "J11") (pin "P2") (pinfunction "2_P2") (pintype "passive"))
      (node (ref "R23") (pin "1") (pinfunction "1_1") (pintype "passive"))
    )
    (net (code "9") (name "Net-(C5-Pad2)") (class "Default")
      (node (ref "C5") (pin "2") (pinfunction "2_2") (pintype "passive"))
      (node (ref "R4") (pin "2") (pinfunction "2_2") (pintype "passive"))
      (node (ref "R5") (pin "2") (pinfunction "2_2") (pintype "passive"))
      (node (ref "SJ1") (pin "2") (pinfunction "2_2") (pintype "passive"))
    )
    (net (code "10") (name "Net-(C8-Pad1)") (class "Default")
      (node (ref "C8") (pin "1") (pinfunction "1_1") (pintype "passive"))
      (node (ref "D4") (pin "C") (pinfunction "C_C") (pintype "passive"))
      (node (ref "R11") (pin "2") (pinfunction "2_2") (pintype "passive"))
    )
    (net (code "11") (name "Net-(C16-Pad2)") (class "Default")
      (node (ref "C16") (pin "2") (pinfunction "2_2") (pintype "passive"))
      (node (ref "R1") (pin "1") (pinfunction "1_1") (pintype "passive"))
      (node (ref "SJ2") (pin "2") (pinfunction "2_2") (pintype "passive"))
    )
    (net (code "12") (name "Net-(C17-Pad1)") (class "Default")
      (node (ref "C17") (pin "1") (pinfunction "1_1") (pintype "passive"))
      (node (ref "R22") (pin "2") (pinfunction "2_2") (pintype "passive"))
    )
    (net (code "13") (name "Net-(C55-Pad1)") (class "Default")
      (node (ref "C55") (pin "1") (pinfunction "1_1") (pintype "passive"))
      (node (ref "R113") (pin "2") (pinfunction "2_2") (pintype "passive"))
      (node (ref "R114") (pin "1") (pinfunction "1_1") (pintype "passive"))
    )
    (net (code "14") (name "Net-(C57-Pad1)") (class "Default")
      (node (ref "C57") (pin "1") (pinfunction "1_1") (pintype "passive"))
      (node (ref "R115") (pin "1") (pinfunction "1_1") (pintype "passive"))
    )
    (net (code "15") (name "Net-(D1-PadA)") (class "Default")
      (node (ref "D1") (pin "A") (pinfunction "A_A") (pintype "passive"))
      (node (ref "JP4") (pin "1") (pinfunction "1_1") (pintype "passive"))
      (node (ref "JP4") (pin "2") (pinfunction "2_2") (pintype "passive"))
    )
    (net (code "16") (name "Net-(D1-PadC)") (class "Default")
      (node (ref "D1") (pin "C") (pinfunction "C_C") (pintype "passive"))
      (node (ref "L1") (pin "2") (pinfunction "2_2") (pintype "passive"))
    )
    (net (code "17") (name "Net-(D2-PadA)") (class "Default")
      (node (ref "D2") (pin "A") (pinfunction "A_A") (pintype "passive"))
      (node (ref "L2") (pin "2") (pinfunction "2_2") (pintype "passive"))
    )
    (net (code "18") (name "Net-(D2-PadC)") (class "Default")
      (node (ref "D2") (pin "C") (pinfunction "C_C") (pintype "passive"))
      (node (ref "JP4") (pin "10") (pinfunction "10_10") (pintype "passive"))
      (node (ref "JP4") (pin "9") (pinfunction "9_9") (pintype "passive"))
    )
    (net (code "19") (name "Net-(D13-PadC)") (class "Default")
      (node (ref "D13") (pin "C") (pinfunction "C_C") (pintype "passive"))
      (node (ref "D14") (pin "C") (pinfunction "C_C") (pintype "passive"))
      (node (ref "R113") (pin "1") (pinfunction "1_1") (pintype "passive"))
    )
    (net (code "20") (name "Net-(IC1A-+IN)") (class "Default")
      (node (ref "IC1") (pin "3") (pinfunction "+IN_3") (pintype "input"))
      (node (ref "R4") (pin "1") (pinfunction "1_1") (pintype "passive"))
    )
    (net (code "21") (name "Net-(IC1A--IN)") (class "Default")
      (node (ref "C7") (pin "1") (pinfunction "1_1") (pintype "passive"))
      (node (ref "IC1") (pin "2") (pinfunction "-IN_2") (pintype "input"))
      (node (ref "R6") (pin "1") (pinfunction "1_1") (pintype "passive"))
      (node (ref "R7") (pin "P$2") (pinfunction "S_P$2") (pintype "passive"))
    )
    (net (code "22") (name "Net-(IC2A-+IN)") (class "Default")
      (node (ref "C17") (pin "2") (pinfunction "2_2") (pintype "passive"))
      (node (ref "IC2") (pin "3") (pinfunction "+IN_3") (pintype "input"))
    )
    (net (code "23") (name "Net-(IC2A--IN)") (class "Default")
      (node (ref "IC2") (pin "1") (pinfunction "OUT_1") (pintype "output"))
      (node (ref "IC2") (pin "2") (pinfunction "-IN_2") (pintype "input"))
      (node (ref "IC2") (pin "5") (pinfunction "+IN_5") (pintype "input"))
      (node (ref "R30") (pin "2") (pinfunction "2_2") (pintype "passive"))
    )
    (net (code "24") (name "Net-(IC2B--IN)") (class "Default")
      (node (ref "C15") (pin "1") (pinfunction "1_1") (pintype "passive"))
      (node (ref "D7") (pin "A") (pinfunction "A_A") (pintype "passive"))
      (node (ref "IC2") (pin "6") (pinfunction "-IN_6") (pintype "input"))
      (node (ref "R31") (pin "1") (pinfunction "1_1") (pintype "passive"))
    )
    (net (code "25") (name "Net-(IC2B-OUT)") (class "Default")
      (node (ref "C15") (pin "2") (pinfunction "2_2") (pintype "passive"))
      (node (ref "D7") (pin "C") (pinfunction "C_C") (pintype "passive"))
      (node (ref "D8") (pin "A") (pinfunction "A_A") (pintype "passive"))
      (node (ref "IC2") (pin "7") (pinfunction "OUT_7") (pintype "output"))
    )
    (net (code "26") (name "Net-(IC2C-+IN)") (class "Default")
      (node (ref "D8") (pin "C") (pinfunction "C_C") (pintype "passive"))
      (node (ref "IC2") (pin "10") (pinfunction "+IN_10") (pintype "input"))
      (node (ref "R32") (pin "2") (pinfunction "2_2") (pintype "passive"))
    )
    (net (code "27") (name "Net-(IC2C--IN)") (class "Default")
      (node (ref "IC2") (pin "9") (pinfunction "-IN_9") (pintype "input"))
      (node (ref "R31") (pin "2") (pinfunction "2_2") (pintype "passive"))
      (node (ref "R34") (pin "1") (pinfunction "1_1") (pintype "passive"))
    )
    (net (code "28") (name "Net-(IC2D-OUT)") (class "Default")
      (node (ref "D4") (pin "A") (pinfunction "A_A") (pintype "passive"))
      (node (ref "IC2") (pin "14") (pinfunction "OUT_14") (pintype "output"))
    )
    (net (code "29") (name "Net-(IC3A--IN)") (class "Default")
      (node (ref "IC3") (pin "2") (pinfunction "-IN_2") (pintype "input"))
      (node (ref "R25") (pin "2") (pinfunction "2_2") (pintype "passive"))
      (node (ref "R29") (pin "1") (pinfunction "1_1") (pintype "passive"))
    )
    (net (code "30") (name "Net-(IC3A-OUT)") (class "Default")
      (node (ref "IC3") (pin "1") (pinfunction "OUT_1") (pintype "output"))
      (node (ref "R26") (pin "1") (pinfunction "1_1") (pintype "passive"))
      (node (ref "R29") (pin "2") (pinfunction "2_2") (pintype "passive"))
    )
    (net (code "31") (name "Net-(IC3B-+IN)") (class "Default")
      (node (ref "IC3") (pin "5") (pinfunction "+IN_5") (pintype "input"))
      (node (ref "R26") (pin "2") (pinfunction "2_2") (pintype "passive"))
      (node (ref "R28") (pin "1") (pinfunction "1_1") (pintype "passive"))
    )
    (net (code "32") (name "Net-(IC3B-OUT)") (class "Default")
      (node (ref "D5") (pin "A") (pinfunction "A_A") (pintype "passive"))
      (node (ref "D6") (pin "C") (pinfunction "C_C") (pintype "passive"))
      (node (ref "IC3") (pin "7") (pinfunction "OUT_7") (pintype "output"))
    )
    (net (code "33") (name "Net-(IC3C--IN)") (class "Default")
      (node (ref "C11") (pin "1") (pinfunction "1_1") (pintype "passive"))
      (node (ref "IC3") (pin "9") (pinfunction "-IN_9") (pintype "input"))
      (node (ref "R18") (pin "P$2") (pinfunction "S_P$2") (pintype "passive"))
      (node (ref "R19") (pin "P$2") (pinfunction "S_P$2") (pintype "passive"))
    )
    (net (code "34") (name "Net-(IC3C-OUT)") (class "Default")
      (node (ref "IC3") (pin "8") (pinfunction "OUT_8") (pintype "output"))
      (node (ref "R28") (pin "2") (pinfunction "2_2") (pintype "passive"))
      (node (ref "R35") (pin "1") (pinfunction "1_1") (pintype "passive"))
    )
    (net (code "35") (name "Net-(IC3D-+IN)") (class "Default")
      (node (ref "IC3") (pin "12") (pinfunction "+IN_12") (pintype "input"))
      (node (ref "R13") (pin "2") (pinfunction "2_2") (pintype "passive"))
    )
    (net (code "36") (name "Net-(IC3D--IN)") (class "Default")
      (node (ref "IC3") (pin "13") (pinfunction "-IN_13") (pintype "input"))
      (node (ref "IC3") (pin "14") (pinfunction "OUT_14") (pintype "output"))
      (node (ref "R25") (pin "1") (pinfunction "1_1") (pintype "passive"))
    )
    (net (code "37") (name "Net-(IC4A-+IN)") (class "Default")
      (node (ref "IC4") (pin "3") (pinfunction "+IN_3") (pintype "input"))
      (node (ref "IC4") (pin "6") (pinfunction "-IN_6") (pintype "input"))
      (node (ref "R115") (pin "2") (pinfunction "2_2") (pintype "passive"))
      (node (ref "R117") (pin "2") (pinfunction "2_2") (pintype "passive"))
      (node (ref "R118") (pin "1") (pinfunction "1_1") (pintype "passive"))
    )
    (net (code "38") (name "Net-(IC4A--IN)") (class "Default")
      (node (ref "IC4") (pin "2") (pinfunction "-IN_2") (pintype "input"))
      (node (ref "R119") (pin "2") (pinfunction "2_2") (pintype "passive"))
      (node (ref "R121") (pin "1") (pinfunction "1_1") (pintype "passive"))
    )
    (net (code "39") (name "Net-(IC4A-OUT)") (class "Default")
      (node (ref "D13") (pin "A") (pinfunction "A_A") (pintype "passive"))
      (node (ref "IC4") (pin "1") (pinfunction "OUT_1") (pintype "output"))
    )
    (net (code "40") (name "Net-(IC4B-+IN)") (class "Default")
      (node (ref "IC4") (pin "5") (pinfunction "+IN_5") (pintype "input"))
      (node (ref "R119") (pin "1") (pinfunction "1_1") (pintype "passive"))
      (node (ref "R120") (pin "2") (pinfunction "2_2") (pintype "passive"))
    )
    (net (code "41") (name "Net-(IC4B-OUT)") (class "Default")
      (node (ref "D14") (pin "A") (pinfunction "A_A") (pintype "passive"))
      (node (ref "IC4") (pin "7") (pinfunction "OUT_7") (pintype "output"))
    )
    (net (code "42") (name "Net-(IC5A--IN)") (class "Default")
      (node (ref "IC5") (pin "2") (pinfunction "-IN_2") (pintype "input"))
      (node (ref "LED3") (pin "K") (pinfunction "C_K") (pintype "passive"))
      (node (ref "R10") (pin "2") (pinfunction "2_2") (pintype "passive"))
    )
    (net (code "43") (name "Net-(IC5A-OUT)") (class "Default")
      (node (ref "IC5") (pin "1") (pinfunction "OUT_1") (pintype "output"))
      (node (ref "LED3") (pin "A") (pinfunction "A_A") (pintype "passive"))
    )
    (net (code "44") (name "Net-(IC5B-+IN)") (class "Default")
      (node (ref "IC5") (pin "5") (pinfunction "+IN_5") (pintype "input"))
      (node (ref "R14") (pin "2") (pinfunction "2_2") (pintype "passive"))
    )
    (net (code "45") (name "Net-(IC5B--IN)") (class "Default")
      (node (ref "IC5") (pin "6") (pinfunction "-IN_6") (pintype "input"))
      (node (ref "IC5") (pin "7") (pinfunction "OUT_7") (pintype "output"))
      (node (ref "R12") (pin "P$2") (pinfunction "S_P$2") (pintype "passive"))
    )
    (net (code "46") (name "Net-(IC5C-+IN)") (class "Default")
      (node (ref "C21") (pin "1") (pinfunction "1_1") (pintype "passive"))
      (node (ref "IC5") (pin "10") (pinfunction "+IN_10") (pintype "input"))
      (node (ref "R12") (pin "P$3") (pinfunction "A_P$3") (pintype "passive"))
    )
    (net (code "47") (name "Net-(IC5D--IN)") (class "Default")
      (node (ref "IC5") (pin "13") (pinfunction "-IN_13") (pintype "input"))
      (node (ref "LED2") (pin "K") (pinfunction "C_K") (pintype "passive"))
      (node (ref "R9") (pin "1") (pinfunction "1_1") (pintype "passive"))
    )
    (net (code "48") (name "Net-(IC5D-OUT)") (class "Default")
      (node (ref "IC5") (pin "14") (pinfunction "OUT_14") (pintype "output"))
      (node (ref "LED2") (pin "A") (pinfunction "A_A") (pintype "passive"))
    )
    (net (code "49") (name "Net-(IC8A-+IN)") (class "Default")
      (node (ref "IC8") (pin "3") (pinfunction "+IN_3") (pintype "input"))
      (node (ref "R15") (pin "2") (pinfunction "2_2") (pintype "passive"))
    )
    (net (code "50") (name "Net-(IC8A--IN)") (class "Default")
      (node (ref "IC8") (pin "2") (pinfunction "-IN_2") (pintype "input"))
      (node (ref "R16") (pin "2") (pinfunction "2_2") (pintype "passive"))
    )
    (net (code "51") (name "Net-(IC8B-OUT)") (class "Default")
      (node (ref "D3") (pin "C") (pinfunction "C_C") (pintype "passive"))
      (node (ref "IC8") (pin "7") (pinfunction "OUT_7") (pintype "output"))
    )
    (net (code "52") (name "Net-(IC8C-OUT)") (class "Default")
      (node (ref "D9") (pin "A") (pinfunction "A_A") (pintype "passive"))
      (node (ref "IC8") (pin "8") (pinfunction "OUT_8") (pintype "output"))
    )
    (net (code "53") (name "Net-(IC8D--IN)") (class "Default")
      (node (ref "IC8") (pin "13") (pinfunction "-IN_13") (pintype "input"))
      (node (ref "LED5") (pin "K") (pinfunction "C_K") (pintype "passive"))
      (node (ref "R17") (pin "1") (pinfunction "1_1") (pintype "passive"))
    )
    (net (code "54") (name "Net-(IC8D-OUT)") (class "Default")
      (node (ref "IC8") (pin "14") (pinfunction "OUT_14") (pintype "output"))
      (node (ref "LED5") (pin "A") (pinfunction "A_A") (pintype "passive"))
    )
    (net (code "55") (name "Net-(IC9A-+IN)") (class "Default")
      (node (ref "IC9") (pin "3") (pinfunction "+IN_3") (pintype "input"))
      (node (ref "R24") (pin "P$2") (pinfunction "S_P$2") (pintype "passive"))
    )
    (net (code "56") (name "Net-(J1-3)") (class "Default")
      (node (ref "C3") (pin "1") (pinfunction "1_1") (pintype "passive"))
      (node (ref "C5") (pin "1") (pinfunction "1_1") (pintype "passive"))
      (node (ref "J1") (pin "P3") (pinfunction "3_P3") (pintype "passive"))
      (node (ref "SJ1") (pin "1") (pinfunction "1_1") (pintype "passive"))
    )
    (net (code "57") (name "Net-(J2-3)") (class "Default")
      (node (ref "J2") (pin "P3") (pinfunction "3_P3") (pintype "passive"))
      (node (ref "R1") (pin "2") (pinfunction "2_2") (pintype "passive"))
    )
    (net (code "58") (name "Net-(J3-3)") (class "Default")
      (node (ref "J3") (pin "P3") (pinfunction "3_P3") (pintype "passive"))
      (node (ref "R2") (pin "2") (pinfunction "2_2") (pintype "passive"))
    )
    (net (code "59") (name "Net-(J4-3)") (class "Default")
      (node (ref "J4") (pin "P3") (pinfunction "3_P3") (pintype "passive"))
      (node (ref "R23") (pin "2") (pinfunction "2_2") (pintype "passive"))
    )
    (net (code "60") (name "Net-(J5-3)") (class "Default")
      (node (ref "J5") (pin "P3") (pinfunction "3_P3") (pintype "passive"))
      (node (ref "R36") (pin "2") (pinfunction "2_2") (pintype "passive"))
    )
    (net (code "61") (name "Net-(J6-3)") (class "Default")
      (node (ref "J6") (pin "P3") (pinfunction "3_P3") (pintype "passive"))
      (node (ref "R22") (pin "1") (pinfunction "1_1") (pintype "passive"))
    )
    (net (code "62") (name "Net-(J7-3)") (class "Default")
      (node (ref "J7") (pin "P3") (pinfunction "3_P3") (pintype "passive"))
      (node (ref "R13") (pin "1") (pinfunction "1_1") (pintype "passive"))
    )
    (net (code "63") (name "Net-(J8-3)") (class "Default")
      (node (ref "J8") (pin "P3") (pinfunction "3_P3") (pintype "passive"))
      (node (ref "R14") (pin "1") (pinfunction "1_1") (pintype "passive"))
    )
    (net (code "64") (name "Net-(J9-3)") (class "Default")
      (node (ref "J9") (pin "P3") (pinfunction "3_P3") (pintype "passive"))
      (node (ref "R33") (pin "2") (pinfunction "2_2") (pintype "passive"))
    )
    (net (code "65") (name "Net-(J10-3)") (class "Default")
      (node (ref "J10") (pin "P3") (pinfunction "3_P3") (pintype "passive"))
      (node (ref "R16") (pin "1") (pinfunction "1_1") (pintype "passive"))
    )
    (net (code "66") (name "Net-(J11-3)") (class "Default")
      (node (ref "J11") (pin "P3") (pinfunction "3_P3") (pintype "passive"))
      (node (ref "R15") (pin "1") (pinfunction "1_1") (pintype "passive"))
    )
    (net (code "67") (name "Net-(J12-3)") (class "Default")
      (node (ref "J12") (pin "P3") (pinfunction "3_P3") (pintype "passive"))
      (node (ref "R27") (pin "2") (pinfunction "2_2") (pintype "passive"))
    )
    (net (code "68") (name "Net-(LED1-PadA)") (class "Default")
      (node (ref "LED1") (pin "A") (pinfunction "A_A") (pintype "passive"))
      (node (ref "R11") (pin "1") (pinfunction "1_1") (pintype "passive"))
    )
    (net (code "69") (name "Net-(LED4-C)") (class "Default")
      (node (ref "LED4") (pin "K") (pinfunction "C_K") (pintype "passive"))
      (node (ref "Q1") (pin "C") (pinfunction "C_C") (pintype "passive"))
    )
    (net (code "70") (name "Net-(LED4-PadA)") (class "Default")
      (node (ref "LED4") (pin "A") (pinfunction "A_A") (pintype "passive"))
      (node (ref "R112") (pin "1") (pinfunction "1_1") (pintype "passive"))
    )
    (net (code "71") (name "Net-(Q1-PadB)") (class "Default")
      (node (ref "Q1") (pin "B") (pinfunction "B_B") (pintype "passive"))
      (node (ref "R114") (pin "2") (pinfunction "2_2") (pintype "passive"))
      (node (ref "R116") (pin "2") (pinfunction "2_2") (pintype "passive"))
    )
    (net (code "72") (name "Net-(R7-E)") (class "Default")
      (node (ref "R7") (pin "P$1") (pinfunction "E_P$1") (pintype "passive"))
      (node (ref "R8") (pin "1") (pinfunction "1_1") (pintype "passive"))
    )
    (net (code "73") (name "Net-(R18-A)") (class "Default")
      (node (ref "D6") (pin "A") (pinfunction "A_A") (pintype "passive"))
      (node (ref "R18") (pin "P$3") (pinfunction "A_P$3") (pintype "passive"))
    )
    (net (code "74") (name "Net-(R19-A)") (class "Default")
      (node (ref "D5") (pin "C") (pinfunction "C_C") (pintype "passive"))
      (node (ref "R19") (pin "P$3") (pinfunction "A_P$3") (pintype "passive"))
    )
    (net (code "75") (name "SLEW") (class "Default")
      (node (ref "C10") (pin "2") (pinfunction "2_2") (pintype "passive"))
      (node (ref "C11") (pin "2") (pinfunction "2_2") (pintype "passive"))
      (node (ref "IC5") (pin "3") (pinfunction "+IN_3") (pintype "input"))
      (node (ref "J8") (pin "P2") (pinfunction "2_P2") (pintype "passive"))
      (node (ref "R2") (pin "1") (pinfunction "1_1") (pintype "passive"))
      (node (ref "R35") (pin "2") (pinfunction "2_2") (pintype "passive"))
    )
    (net (code "76") (name "THRESH") (class "Default")
      (node (ref "IC9") (pin "1") (pinfunction "OUT_1") (pintype "output"))
      (node (ref "IC9") (pin "2") (pinfunction "-IN_2") (pintype "input"))
      (node (ref "J10") (pin "P2") (pinfunction "2_P2") (pintype "passive"))
      (node (ref "R27") (pin "1") (pinfunction "1_1") (pintype "passive"))
    )
    (net (code "77") (name "VCC") (class "Default")
      (node (ref "C1") (pin "1") (pinfunction "1_1") (pintype "passive"))
      (node (ref "C13") (pin "1") (pinfunction "1_1") (pintype "passive"))
      (node (ref "C19") (pin "1") (pinfunction "1_1") (pintype "passive"))
      (node (ref "C23") (pin "1") (pinfunction "1_1") (pintype "passive"))
      (node (ref "C25") (pin "1") (pinfunction "1_1") (pintype "passive"))
      (node (ref "C56") (pin "1") (pinfunction "1_1") (pintype "passive"))
      (node (ref "C58") (pin "+") (pinfunction "+_+") (pintype "passive"))
      (node (ref "C6") (pin "1") (pinfunction "1_1") (pintype "passive"))
      (node (ref "C9") (pin "1") (pinfunction "1_1") (pintype "passive"))
      (node (ref "IC1") (pin "7") (pinfunction "V+_7") (pintype "power_in"))
      (node (ref "IC2") (pin "4") (pinfunction "V+_4") (pintype "power_in"))
      (node (ref "IC3") (pin "4") (pinfunction "V+_4") (pintype "power_in"))
      (node (ref "IC4") (pin "8") (pinfunction "V+_8") (pintype "power_in"))
      (node (ref "IC5") (pin "4") (pinfunction "V+_4") (pintype "power_in"))
      (node (ref "IC8") (pin "4") (pinfunction "V+_4") (pintype "power_in"))
      (node (ref "IC9") (pin "4") (pinfunction "V+_4") (pintype "power_in"))
      (node (ref "L1") (pin "1") (pinfunction "1_1") (pintype "passive"))
      (node (ref "R112") (pin "2") (pinfunction "2_2") (pintype "passive"))
      (node (ref "R20") (pin "1") (pinfunction "1_1") (pintype "passive"))
      (node (ref "R3") (pin "1") (pinfunction "1_1") (pintype "passive"))
    )
    (net (code "78") (name "VEE") (class "Default")
      (node (ref "C12") (pin "2") (pinfunction "2_2") (pintype "passive"))
      (node (ref "C18") (pin "2") (pinfunction "2_2") (pintype "passive"))
      (node (ref "C2") (pin "2") (pinfunction "2_2") (pintype "passive"))
      (node (ref "C20") (pin "2") (pinfunction "2_2") (pintype "passive"))
      (node (ref "C24") (pin "2") (pinfunction "2_2") (pintype "passive"))
      (node (ref "C26") (pin "2") (pinfunction "2_2") (pintype "passive"))
      (node (ref "C4") (pin "2") (pinfunction "2_2") (pintype "passive"))
      (node (ref "IC1") (pin "4") (pinfunction "V-_4") (pintype "power_in"))
      (node (ref "IC2") (pin "11") (pinfunction "V-_11") (pintype "power_in"))
      (node (ref "IC3") (pin "11") (pinfunction "V-_11") (pintype "power_in"))
      (node (ref "IC5") (pin "11") (pinfunction "V-_11") (pintype "power_in"))
      (node (ref "IC8") (pin "11") (pinfunction "V-_11") (pintype "power_in"))
      (node (ref "IC9") (pin "11") (pinfunction "V-_11") (pintype "power_in"))
      (node (ref "L2") (pin "1") (pinfunction "1_1") (pintype "passive"))
    )
    (net (code "79") (name "unconnected-(C10-Pad1)") (class "Default")
      (node (ref "C10") (pin "1") (pinfunction "1_1") (pintype "passive"))
    )
    (net (code "80") (name "unconnected-(IC9B-+IN-Pad5)") (class "Default")
      (node (ref "IC9") (pin "5") (pinfunction "+IN_5") (pintype "input"))
    )
    (net (code "81") (name "unconnected-(IC9B--IN-Pad6)") (class "Default")
      (node (ref "IC9") (pin "6") (pinfunction "-IN_6") (pintype "input"))
    )
    (net (code "82") (name "unconnected-(IC9B-OUT-Pad7)") (class "Default")
      (node (ref "IC9") (pin "7") (pinfunction "OUT_7") (pintype "output"))
    )
    (net (code "83") (name "unconnected-(IC9C-+IN-Pad10)") (class "Default")
      (node (ref "IC9") (pin "10") (pinfunction "+IN_10") (pintype "input"))
    )
    (net (code "84") (name "unconnected-(IC9C--IN-Pad9)") (class "Default")
      (node (ref "IC9") (pin "9") (pinfunction "-IN_9") (pintype "input"))
    )
    (net (code "85") (name "unconnected-(IC9C-OUT-Pad8)") (class "Default")
      (node (ref "IC9") (pin "8") (pinfunction "OUT_8") (pintype "output"))
    )
    (net (code "86") (name "unconnected-(IC9D-+IN-Pad12)") (class "Default")
      (node (ref "IC9") (pin "12") (pinfunction "+IN_12") (pintype "input"))
    )
    (net (code "87") (name "unconnected-(IC9D--IN-Pad13)") (class "Default")
      (node (ref "IC9") (pin "13") (pinfunction "-IN_13") (pintype "input"))
    )
    (net (code "88") (name "unconnected-(IC9D-OUT-Pad14)") (class "Default")
      (node (ref "IC9") (pin "14") (pinfunction "OUT_14") (pintype "output"))
    )
    (net (code "89") (name "unconnected-(J1-2-PadP2)") (class "Default")
      (node (ref "J1") (pin "P2") (pinfunction "2_P2") (pintype "passive"))
    )
    (net (code "90") (name "unconnected-(J2-2-PadP2)") (class "Default")
      (node (ref "J2") (pin "P2") (pinfunction "2_P2") (pintype "passive"))
    )
    (net (code "91") (name "unconnected-(J3-2-PadP2)") (class "Default")
      (node (ref "J3") (pin "P2") (pinfunction "2_P2") (pintype "passive"))
    )
    (net (code "92") (name "unconnected-(J4-2-PadP2)") (class "Default")
      (node (ref "J4") (pin "P2") (pinfunction "2_P2") (pintype "passive"))
    )
    (net (code "93") (name "unconnected-(J5-2-PadP2)") (class "Default")
      (node (ref "J5") (pin "P2") (pinfunction "2_P2") (pintype "passive"))
    )
    (net (code "94") (name "unconnected-(J9-2-PadP2)") (class "Default")
      (node (ref "J9") (pin "P2") (pinfunction "2_P2") (pintype "passive"))
    )
    (net (code "95") (name "unconnected-(J12-2-PadP2)") (class "Default")
      (node (ref "J12") (pin "P2") (pinfunction "2_P2") (pintype "passive"))
    )
    (net (code "96") (name "unconnected-(R12-E-PadP$1)") (class "Default")
      (node (ref "R12") (pin "P$1") (pinfunction "E_P$1") (pintype "passive"))
    )
    (net (code "97") (name "unconnected-(R18-E-PadP$1)") (class "Default")
      (node (ref "R18") (pin "P$1") (pinfunction "E_P$1") (pintype "passive"))
    )
    (net (code "98") (name "unconnected-(R19-E-PadP$1)") (class "Default")
      (node (ref "R19") (pin "P$1") (pinfunction "E_P$1") (pintype "passive"))
    )
    (net (code "99") (name "unconnected-(R24-E-PadP$1)") (class "Default")
      (node (ref "R24") (pin "P$1") (pinfunction "E_P$1") (pintype "passive"))
    )
  )
)
